# IRIS1304_v4_0.net
KiCad netlist of a schematic drawn in EAGLE
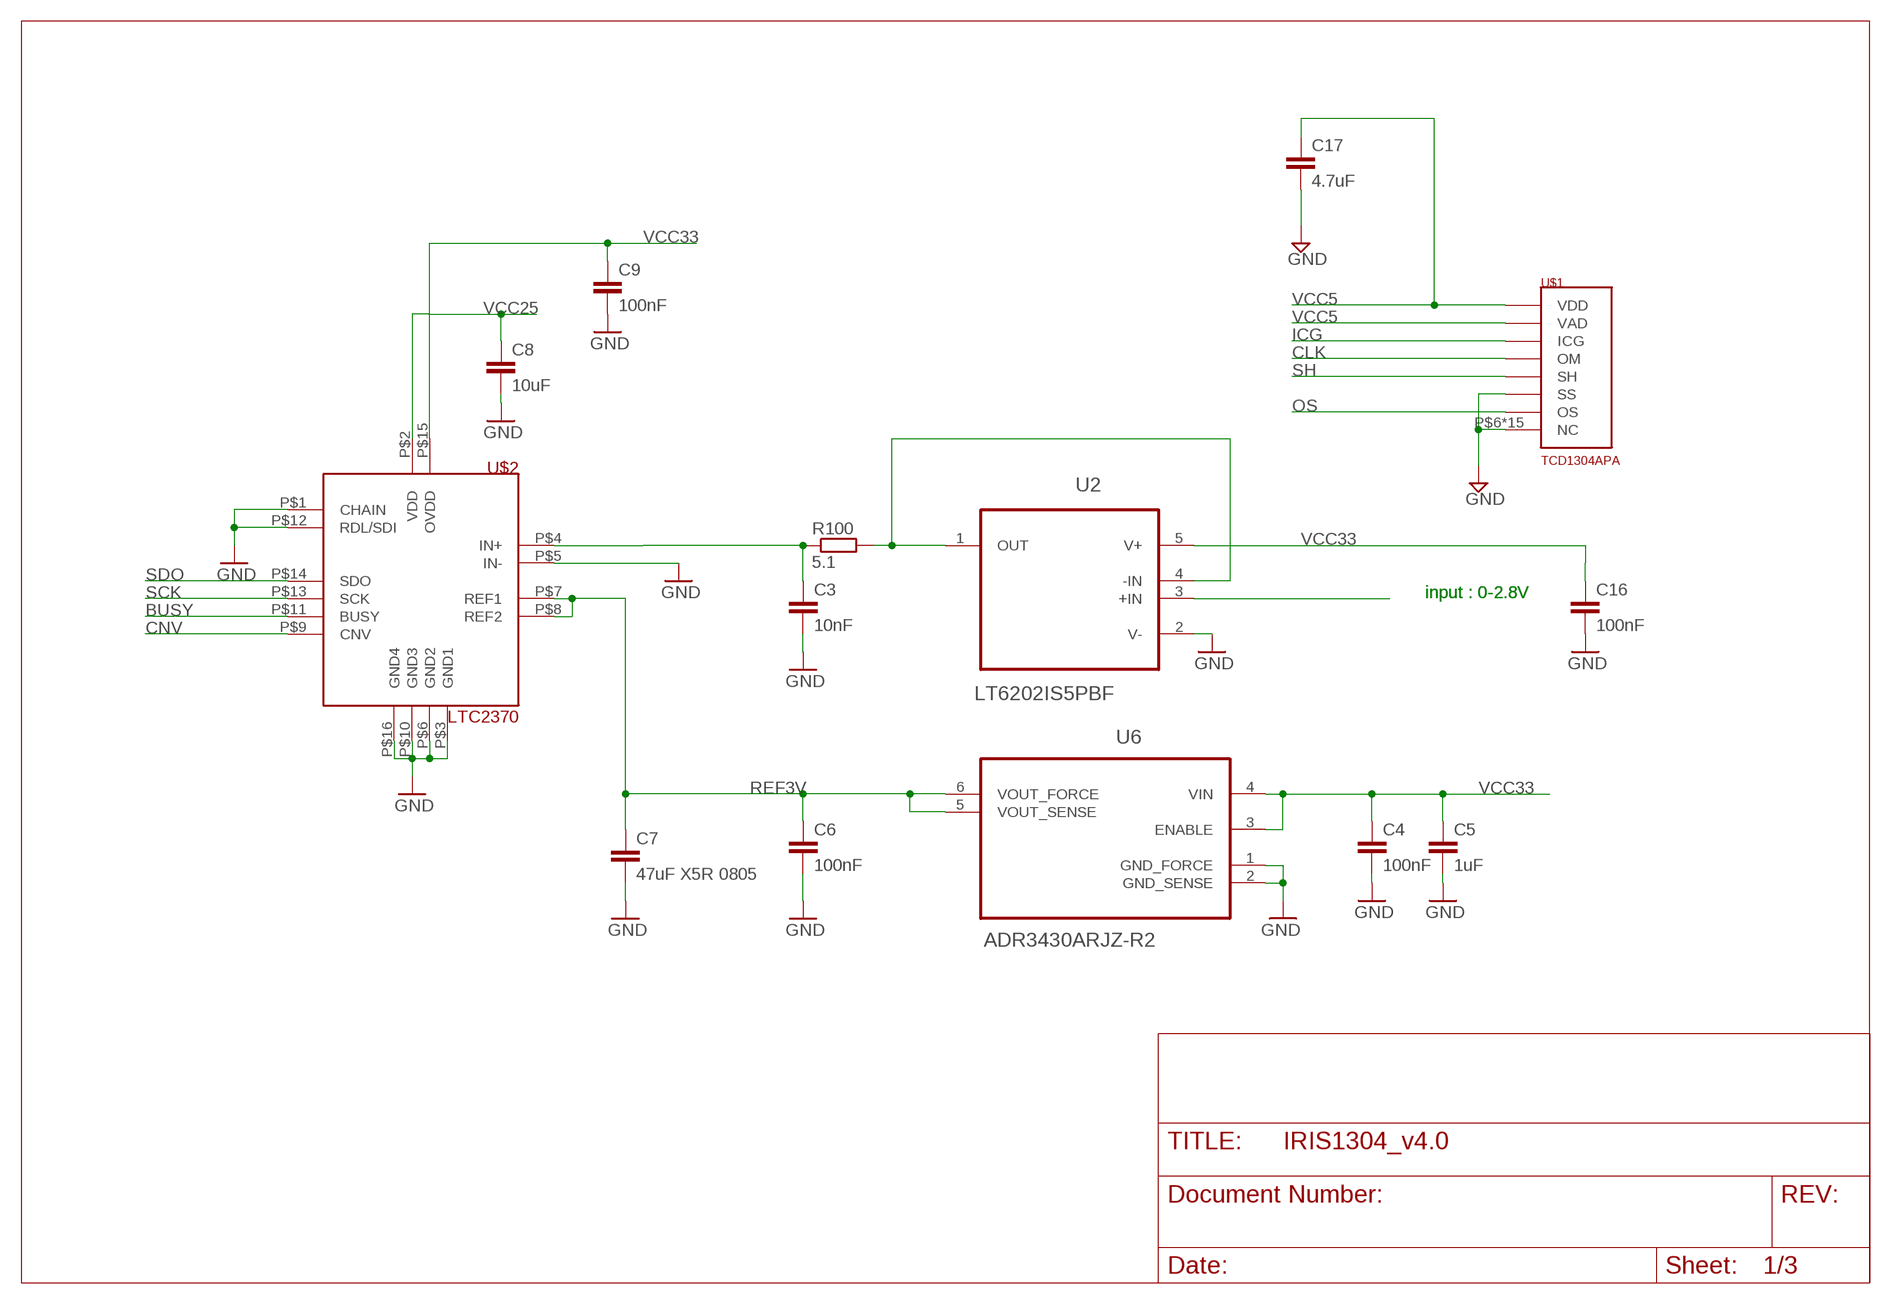
[diagram p0: schematic, sheet 1]
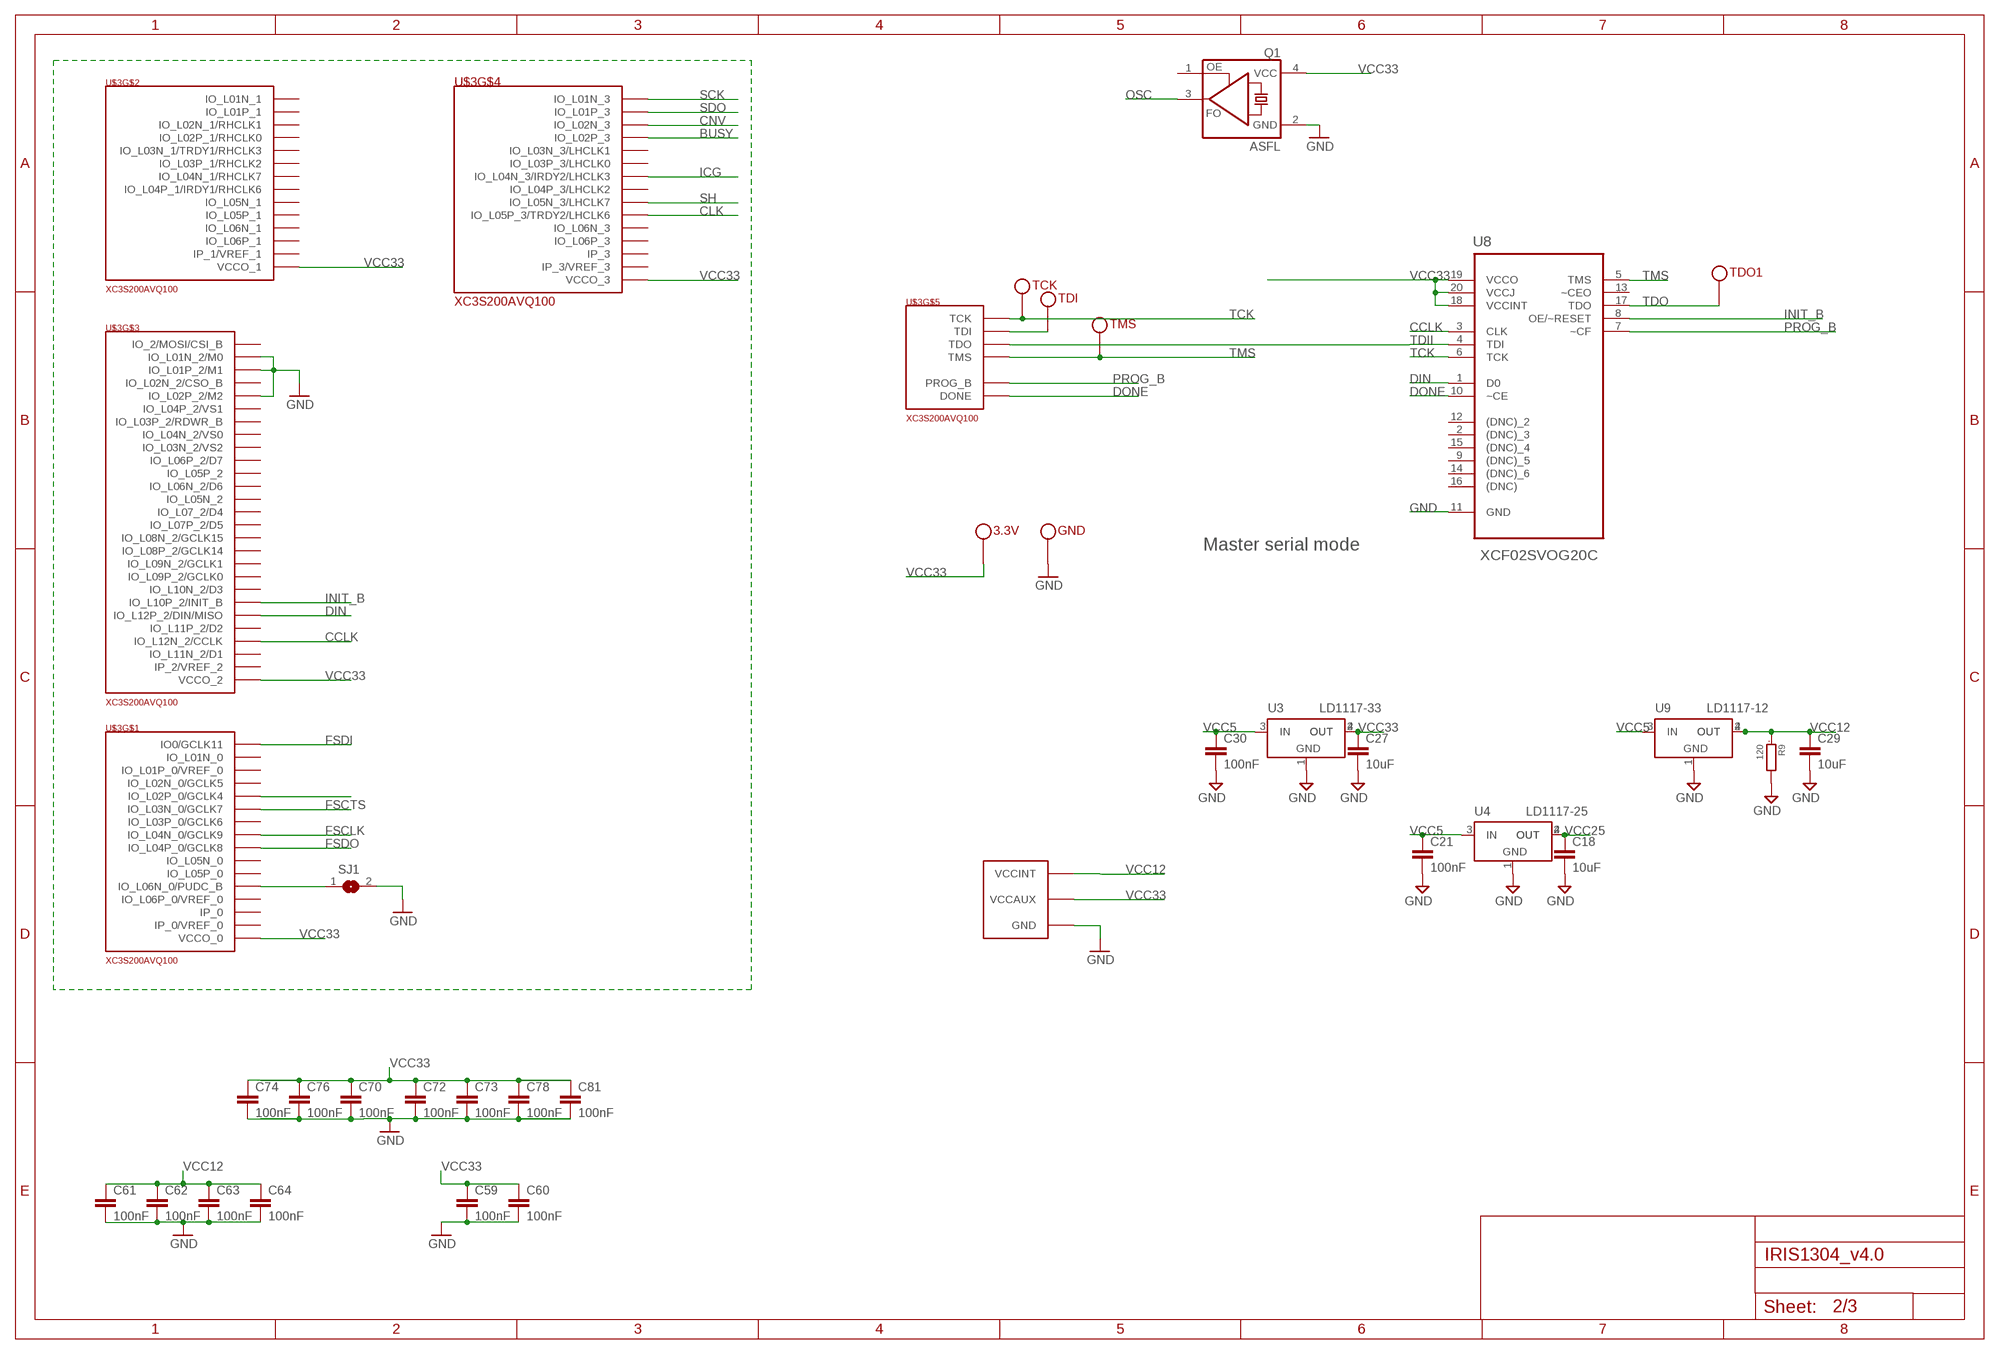
[diagram p1: schematic, sheet 2]
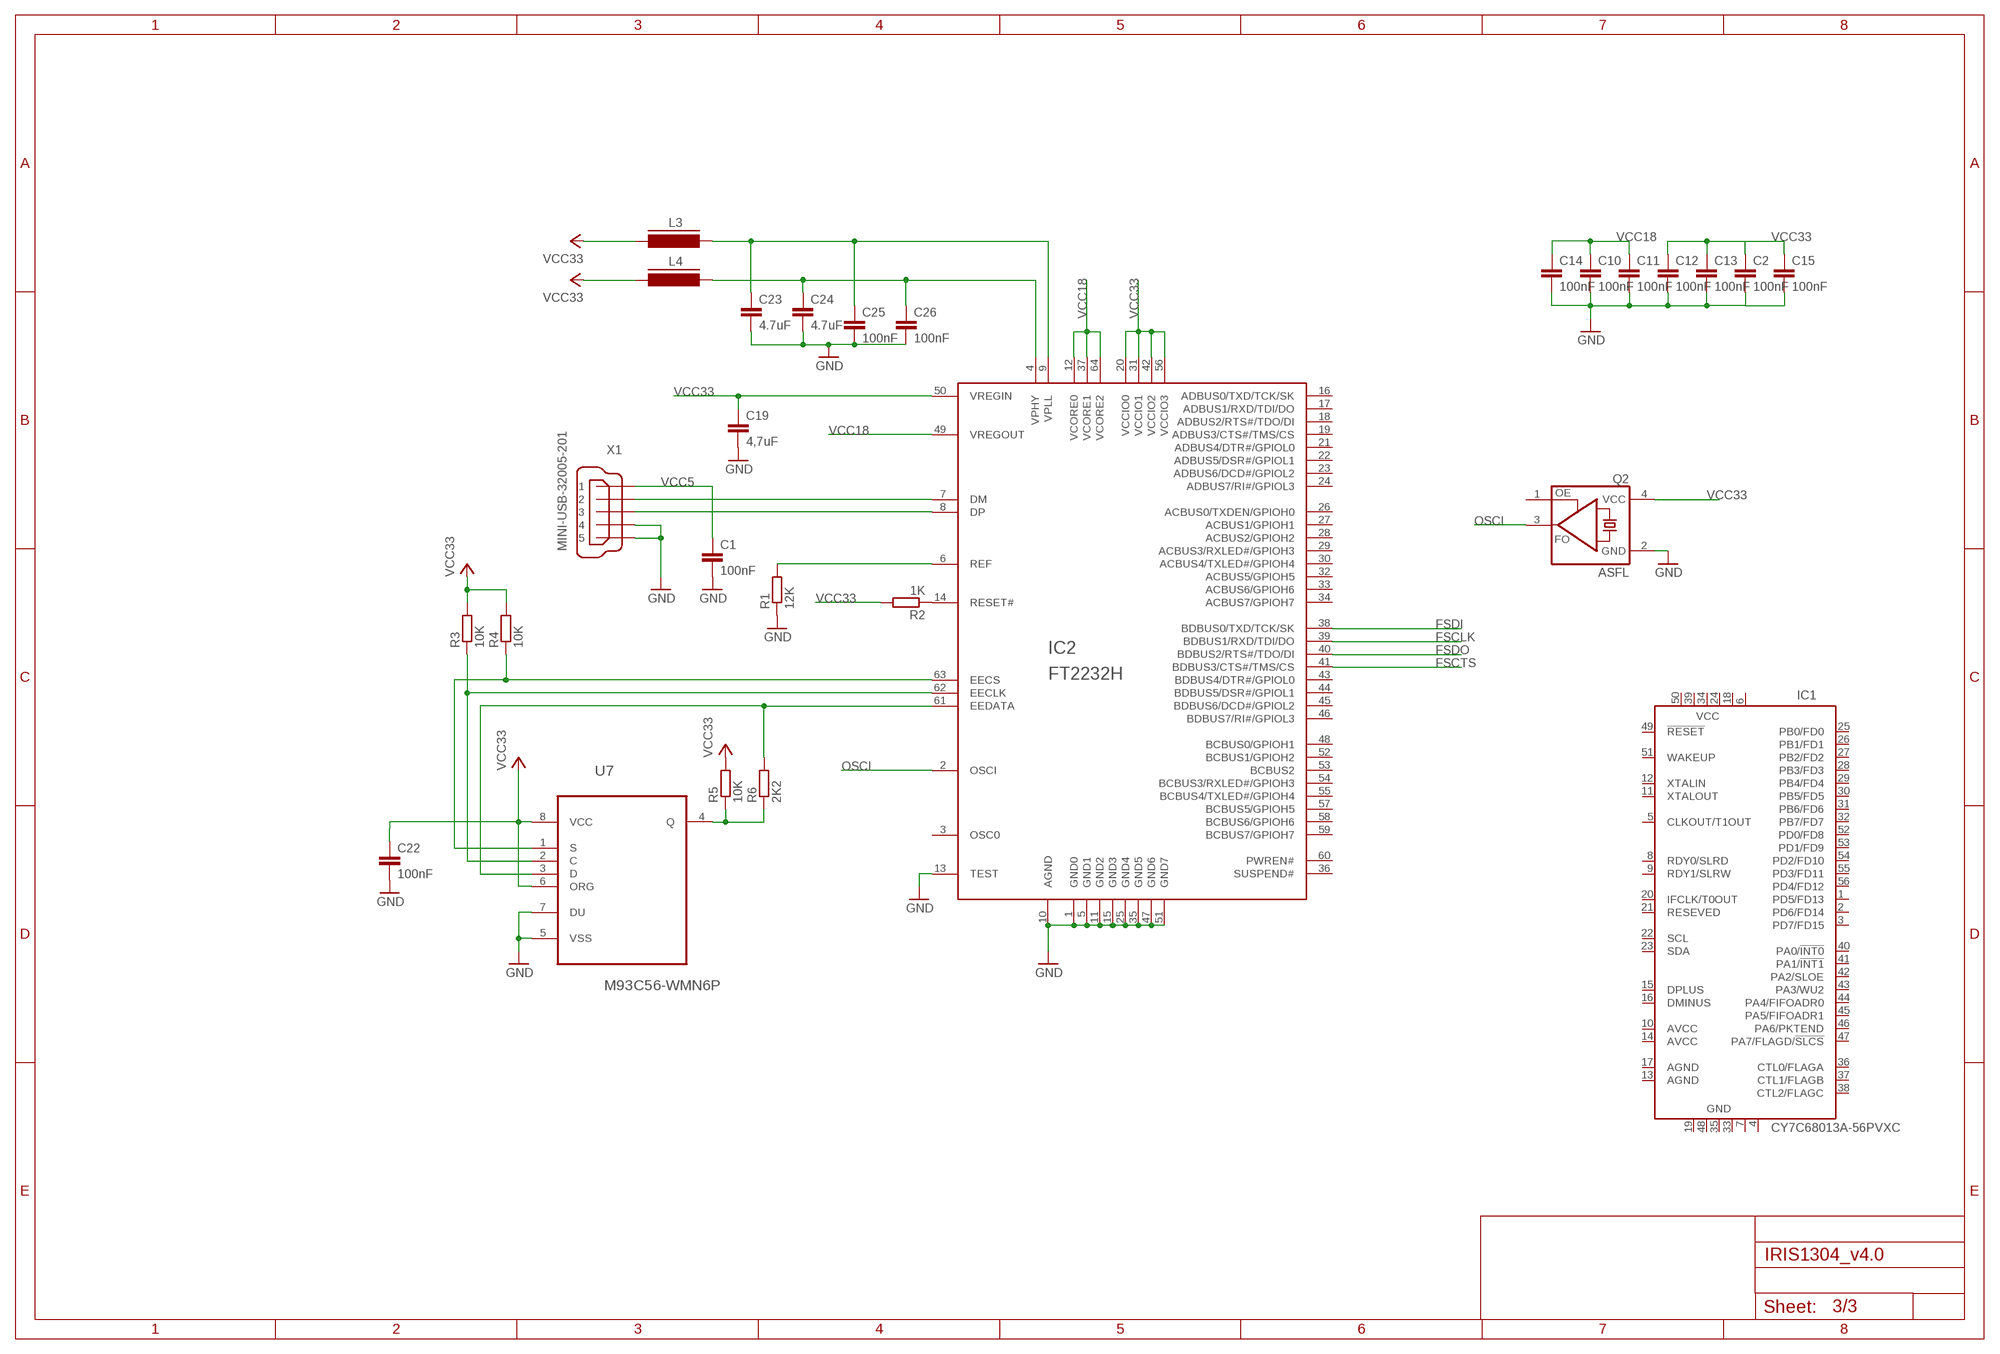
[diagram p2: schematic, sheet 3]

(export (version "E")
  (design (tool "Eeschema 10.0.6"))
  (components
    (comp (ref "C1")
      (value "100nF")
      (footprint "eagle-import:C0603")
      (fields (field (name "MF") "AVX") (field (name "MPN") "06033G104ZAT2A"))
      (libsource (lib "eagle-import") (part "C-EUC0603"))
    )
    (comp (ref "C2")
      (value "100nF")
      (footprint "eagle-import:C0603")
      (fields (field (name "MF") "AVX") (field (name "MPN") "06033G104ZAT2A"))
      (libsource (lib "eagle-import") (part "C-EUC0603"))
    )
    (comp (ref "C10")
      (value "100nF")
      (footprint "eagle-import:C0603")
      (fields (field (name "MF") "AVX") (field (name "MPN") "06033G104ZAT2A"))
      (libsource (lib "eagle-import") (part "C-EUC0603"))
    )
    (comp (ref "C11")
      (value "100nF")
      (footprint "eagle-import:C0603")
      (fields (field (name "MF") "AVX") (field (name "MPN") "06033G104ZAT2A"))
      (libsource (lib "eagle-import") (part "C-EUC0603"))
    )
    (comp (ref "C12")
      (value "100nF")
      (footprint "eagle-import:C0603")
      (fields (field (name "MF") "AVX") (field (name "MPN") "06033G104ZAT2A"))
      (libsource (lib "eagle-import") (part "C-EUC0603"))
    )
    (comp (ref "C13")
      (value "100nF")
      (footprint "eagle-import:C0603")
      (fields (field (name "MF") "AVX") (field (name "MPN") "06033G104ZAT2A"))
      (libsource (lib "eagle-import") (part "C-EUC0603"))
    )
    (comp (ref "C14")
      (value "100nF")
      (footprint "eagle-import:C0603")
      (fields (field (name "MF") "AVX") (field (name "MPN") "06033G104ZAT2A"))
      (libsource (lib "eagle-import") (part "C-EUC0603"))
    )
    (comp (ref "C15")
      (value "100nF")
      (footprint "eagle-import:C0603")
      (fields (field (name "MF") "AVX") (field (name "MPN") "06033G104ZAT2A"))
      (libsource (lib "eagle-import") (part "C-EUC0603"))
    )
    (comp (ref "C19")
      (value "4,7uF")
      (footprint "eagle-import:C0805")
      (fields (field (name "MF") "AVX") (field (name "MPN") "0805ZD335KAT2A"))
      (libsource (lib "eagle-import") (part "C-EUC0805"))
    )
    (comp (ref "C22")
      (value "100nF")
      (footprint "eagle-import:C0603")
      (fields (field (name "MF") "AVX") (field (name "MPN") "06033G104ZAT2A"))
      (libsource (lib "eagle-import") (part "C-EUC0603"))
    )
    (comp (ref "C23")
      (value "4.7uF")
      (footprint "eagle-import:C0603")
      (fields (field (name "MF") "YAGEO (PHYCOMP)") (field (name "MPN") "CC0603KRX5R6BB475"))
      (libsource (lib "eagle-import") (part "C-EUC0603"))
    )
    (comp (ref "C24")
      (value "4.7uF")
      (footprint "eagle-import:C0603")
      (fields (field (name "MF") "YAGEO (PHYCOMP)") (field (name "MPN") "CC0603KRX5R6BB475"))
      (libsource (lib "eagle-import") (part "C-EUC0603"))
    )
    (comp (ref "C25")
      (value "100nF")
      (footprint "eagle-import:C0603")
      (fields (field (name "MF") "AVX") (field (name "MPN") "06033G104ZAT2A"))
      (libsource (lib "eagle-import") (part "C-EUC0603"))
    )
    (comp (ref "C26")
      (value "100nF")
      (footprint "eagle-import:C0603")
      (fields (field (name "MF") "AVX") (field (name "MPN") "06033G104ZAT2A"))
      (libsource (lib "eagle-import") (part "C-EUC0603"))
    )
    (comp (ref "IC1")
      (value "CY7C68013A-56PVXC")
      (footprint "eagle-import:SSOP56")
      (fields (field (name "MF") "CYPRESS SEMICONDUCTOR CORPORAT"))
      (libsource (lib "eagle-import") (part "CY7C6801A-56PVXC3"))
    )
    (comp (ref "IC2")
      (value "FT2232H")
      (footprint "eagle-import:LQFP64")
      (fields (field (name "MF") "FTDI") (field (name "MPN") "FT2232HL-R"))
      (libsource (lib "eagle-import") (part "FT2232H"))
    )
    (comp (ref "L3")
      (value "FERRITE_BEAD805")
      (footprint "eagle-import:FB805")
      (libsource (lib "eagle-import") (part "FERRITE_BEAD805"))
    )
    (comp (ref "L4")
      (value "FERRITE_BEAD805")
      (footprint "eagle-import:FB805")
      (libsource (lib "eagle-import") (part "FERRITE_BEAD805"))
    )
    (comp (ref "Q2")
      (value "ASFL")
      (footprint "eagle-import:ASF")
      (fields
        (field (name "MPN") "ASFLM1-50.000MHZ-C-T")
        (field (name "MF") "ABRACON")
        (field (name "MPN_1") "ASFL1-12.000MHZ-EK-T")
        (field (name "OC_FARNELL") "7943088")
      )
      (libsource (lib "eagle-import") (part "ASFL"))
    )
    (comp (ref "R1")
      (value "12K")
      (footprint "eagle-import:R0603")
      (fields (field (name "MF") "TE CONNECTIVITY") (field (name "MPN") "CPF0201D12K1C1"))
      (libsource (lib "eagle-import") (part "R-EU_R0603"))
    )
    (comp (ref "R2")
      (value "1K")
      (footprint "eagle-import:R0603")
      (fields (field (name "MF") "VISHAY DRALORIC") (field (name "MPN") "CRCW06031K00FKEA"))
      (libsource (lib "eagle-import") (part "R-EU_R0603"))
    )
    (comp (ref "R3")
      (value "10K")
      (footprint "eagle-import:R0603")
      (fields (field (name "MF") "TE CONNECTIVITY / NEOHM") (field (name "MPN") "CPF0603F10KC1"))
      (libsource (lib "eagle-import") (part "R-EU_R0603"))
    )
    (comp (ref "R4")
      (value "10K")
      (footprint "eagle-import:R0603")
      (fields (field (name "MF") "TE CONNECTIVITY / NEOHM") (field (name "MPN") "CPF0603F10KC1"))
      (libsource (lib "eagle-import") (part "R-EU_R0603"))
    )
    (comp (ref "R5")
      (value "10K")
      (footprint "eagle-import:R0603")
      (fields (field (name "MF") "TE CONNECTIVITY / NEOHM") (field (name "MPN") "CPF0603F10KC1"))
      (libsource (lib "eagle-import") (part "R-EU_R0603"))
    )
    (comp (ref "R6")
      (value "2K2")
      (footprint "eagle-import:R0603")
      (fields (field (name "MF") "PANASONIC ELECTRONIC COMPONENTS") (field (name "MPN") "ERJP03F2201V"))
      (libsource (lib "eagle-import") (part "R-EU_R0603"))
    )
    (comp (ref "U7")
      (value "M93C56-WMN6P")
      (footprint "eagle-import:SOIC127P600X175-8N")
      (fields (field (name "MF") "STMICROELECTRONICS"))
      (libsource (lib "eagle-import") (part "M93C56-WMN6P"))
    )
    (comp (ref "X1")
      (value "MINI-USB-32005-201")
      (footprint "eagle-import:32005-201")
      (fields
        (field (name "MF") "WURTH ELEKTRONIK")
        (field (name "MPN") "65100516121")
        (field (name "OC_FARNELL") "1642036")
      )
      (libsource (lib "eagle-import") (part "MINI-USB-32005-201"))
    )
    (comp (ref "C3")
      (value "10nF")
      (footprint "eagle-import:C0603")
      (fields (field (name "MF") "AVX") (field (name "MPN") "06035G103ZAT2A"))
      (libsource (lib "eagle-import") (part "C-EUC0603"))
    )
    (comp (ref "C4")
      (value "100nF")
      (footprint "eagle-import:C0603")
      (fields (field (name "MF") "AVX") (field (name "MPN") "06033G104ZAT2A"))
      (libsource (lib "eagle-import") (part "C-EUC0603"))
    )
    (comp (ref "C5")
      (value "1uF")
      (footprint "eagle-import:C0603")
      (fields (field (name "MF") "KEMET") (field (name "MPN") "C0603C105K3PACTU"))
      (libsource (lib "eagle-import") (part "C-EUC0603"))
    )
    (comp (ref "C6")
      (value "100nF")
      (footprint "eagle-import:C0603")
      (fields (field (name "MF") "AVX") (field (name "MPN") "06033G104ZAT2A"))
      (libsource (lib "eagle-import") (part "C-EUC0603"))
    )
    (comp (ref "C7")
      (value "47uF X5R 0805")
      (footprint "eagle-import:C0805")
      (fields (field (name "MF") "KEMET") (field (name "MPN") "C0805C476M9PACTU"))
      (libsource (lib "eagle-import") (part "C-EUC0805"))
    )
    (comp (ref "C8")
      (value "10uF")
      (footprint "eagle-import:C0603")
      (fields (field (name "MF") "KEMET") (field (name "MPN") "C0603C106M9PACTU"))
      (libsource (lib "eagle-import") (part "C-EUC0603"))
    )
    (comp (ref "C9")
      (value "100nF")
      (footprint "eagle-import:C0603")
      (fields (field (name "MF") "AVX") (field (name "MPN") "06033G104ZAT2A"))
      (libsource (lib "eagle-import") (part "C-EUC0603"))
    )
    (comp (ref "C16")
      (value "100nF")
      (footprint "eagle-import:C0603")
      (fields (field (name "MF") "AVX") (field (name "MPN") "06033G104ZAT2A"))
      (libsource (lib "eagle-import") (part "C-EUC0603"))
    )
    (comp (ref "C17")
      (value "4.7uF")
      (footprint "eagle-import:C0603")
      (fields (field (name "MF") "YAGEO (PHYCOMP)") (field (name "MPN") "CC0603KRX5R6BB475"))
      (libsource (lib "eagle-import") (part "C-EUC0603"))
    )
    (comp (ref "R100")
      (value "5.1")
      (footprint "eagle-import:R0603")
      (fields (field (name "MF") "VISHAY DALE") (field (name "MPN") "CRCW06035R10FNEA"))
      (libsource (lib "eagle-import") (part "R-EU_R0603"))
    )
    (comp (ref "U$1")
      (value "TCD1304APA")
      (footprint "eagle-import:ILX511")
      (libsource (lib "eagle-import") (part "TCD1304APA"))
    )
    (comp (ref "U$2")
      (value "LTC2370")
      (footprint "eagle-import:MSOP-16")
      (fields (field (name "MF") "LINEAR TECHNOLOGY") (field (name "MPN") "LTC2370CMS-16"))
      (libsource (lib "eagle-import") (part "LTC2370"))
    )
    (comp (ref "U2")
      (value "LT6202IS5PBF")
      (footprint "eagle-import:SOT95P280X100-5N")
      (fields (field (name "MPN") "LT6202IS5#PBF") (field (name "MF") "LINEAR TECHNOLOGY"))
      (libsource (lib "eagle-import") (part "LT6202IS5PBF"))
    )
    (comp (ref "U6")
      (value "ADR3430ARJZ-R2")
      (footprint "eagle-import:SOT95P280X145-6N")
      (fields (field (name "MF") "ANALOG DEVICES"))
      (libsource (lib "eagle-import") (part "ADR3430ARJZ-R2"))
    )
    (comp (ref "3.3V")
      (value "TEST")
      (footprint "eagle-import:TEST")
      (fields (field (name "MF") "ITT CANNON") (field (name "MPN") "001-1007-040FB9"))
      (libsource (lib "eagle-import") (part "TEST"))
    )
    (comp (ref "C18")
      (value "10uF")
      (footprint "eagle-import:C0603")
      (fields (field (name "MF") "KEMET") (field (name "MPN") "C0603C106M9PACTU"))
      (libsource (lib "eagle-import") (part "C-EUC0603"))
    )
    (comp (ref "C21")
      (value "100nF")
      (footprint "eagle-import:C0603")
      (fields (field (name "MF") "AVX") (field (name "MPN") "06033G104ZAT2A"))
      (libsource (lib "eagle-import") (part "C-EUC0603"))
    )
    (comp (ref "C27")
      (value "10uF")
      (footprint "eagle-import:C0603")
      (fields (field (name "MF") "KEMET") (field (name "MPN") "C0603C106M9PACTU"))
      (libsource (lib "eagle-import") (part "C-EUC0603"))
    )
    (comp (ref "C29")
      (value "10uF")
      (footprint "eagle-import:C0603")
      (fields (field (name "MF") "KEMET") (field (name "MPN") "C0603C106M9PACTU"))
      (libsource (lib "eagle-import") (part "C-EUC0603"))
    )
    (comp (ref "C30")
      (value "100nF")
      (footprint "eagle-import:C0603")
      (fields (field (name "MF") "AVX") (field (name "MPN") "06033G104ZAT2A"))
      (libsource (lib "eagle-import") (part "C-EUC0603"))
    )
    (comp (ref "C59")
      (value "100nF")
      (footprint "eagle-import:C0603")
      (fields (field (name "MF") "AVX") (field (name "MPN") "06033G104ZAT2A"))
      (libsource (lib "eagle-import") (part "C-EUC0603"))
    )
    (comp (ref "C60")
      (value "100nF")
      (footprint "eagle-import:C0603")
      (fields (field (name "MF") "AVX") (field (name "MPN") "06033G104ZAT2A"))
      (libsource (lib "eagle-import") (part "C-EUC0603"))
    )
    (comp (ref "C61")
      (value "100nF")
      (footprint "eagle-import:C0603")
      (fields (field (name "MF") "AVX") (field (name "MPN") "06033G104ZAT2A"))
      (libsource (lib "eagle-import") (part "C-EUC0603"))
    )
    (comp (ref "C62")
      (value "100nF")
      (footprint "eagle-import:C0603")
      (fields (field (name "MF") "AVX") (field (name "MPN") "06033G104ZAT2A"))
      (libsource (lib "eagle-import") (part "C-EUC0603"))
    )
    (comp (ref "C63")
      (value "100nF")
      (footprint "eagle-import:C0603")
      (fields (field (name "MF") "AVX") (field (name "MPN") "06033G104ZAT2A"))
      (libsource (lib "eagle-import") (part "C-EUC0603"))
    )
    (comp (ref "C64")
      (value "100nF")
      (footprint "eagle-import:C0603")
      (fields (field (name "MF") "AVX") (field (name "MPN") "06033G104ZAT2A"))
      (libsource (lib "eagle-import") (part "C-EUC0603"))
    )
    (comp (ref "C70")
      (value "100nF")
      (footprint "eagle-import:C0603")
      (fields (field (name "MF") "AVX") (field (name "MPN") "06033G104ZAT2A"))
      (libsource (lib "eagle-import") (part "C-EUC0603"))
    )
    (comp (ref "C72")
      (value "100nF")
      (footprint "eagle-import:C0603")
      (fields (field (name "MF") "AVX") (field (name "MPN") "06033G104ZAT2A"))
      (libsource (lib "eagle-import") (part "C-EUC0603"))
    )
    (comp (ref "C73")
      (value "100nF")
      (footprint "eagle-import:C0603")
      (fields (field (name "MF") "AVX") (field (name "MPN") "06033G104ZAT2A"))
      (libsource (lib "eagle-import") (part "C-EUC0603"))
    )
    (comp (ref "C74")
      (value "100nF")
      (footprint "eagle-import:C0603")
      (fields (field (name "MF") "AVX") (field (name "MPN") "06033G104ZAT2A"))
      (libsource (lib "eagle-import") (part "C-EUC0603"))
    )
    (comp (ref "C76")
      (value "100nF")
      (footprint "eagle-import:C0603")
      (fields (field (name "MF") "AVX") (field (name "MPN") "06033G104ZAT2A"))
      (libsource (lib "eagle-import") (part "C-EUC0603"))
    )
    (comp (ref "C78")
      (value "100nF")
      (footprint "eagle-import:C0603")
      (fields (field (name "MF") "AVX") (field (name "MPN") "06033G104ZAT2A"))
      (libsource (lib "eagle-import") (part "C-EUC0603"))
    )
    (comp (ref "C81")
      (value "100nF")
      (footprint "eagle-import:C0603")
      (fields (field (name "MF") "AVX") (field (name "MPN") "06033G104ZAT2A"))
      (libsource (lib "eagle-import") (part "C-EUC0603"))
    )
    (comp (ref "GND")
      (value "TEST")
      (footprint "eagle-import:TEST")
      (fields (field (name "MF") "ITT CANNON") (field (name "MPN") "001-1007-040FB9"))
      (libsource (lib "eagle-import") (part "TEST"))
    )
    (comp (ref "Q1")
      (value "ASFL")
      (footprint "eagle-import:ASF")
      (fields
        (field (name "MPN") "ASFLM1-50.000MHZ-C-T")
        (field (name "MF") "ABRACON")
        (field (name "MPN_1") "ASFL1-12.000MHZ-EK-T")
        (field (name "OC_FARNELL") "7943088")
      )
      (libsource (lib "eagle-import") (part "ASFL"))
    )
    (comp (ref "R9")
      (value "120")
      (footprint "eagle-import:0805@1")
      (fields (field (name "MF") "TE CONNECTIVITY / SIGMA INDUCTORS") (field (name "MPN") "BMB2A0120AN1"))
      (libsource (lib "eagle-import") (part "R0805"))
    )
    (comp (ref "SJ1") (value "SJ") (footprint "eagle-import:SJ") (libsource (lib "eagle-import") (part "SJ")))
    (comp (ref "TCK")
      (value "TEST")
      (footprint "eagle-import:TEST")
      (fields (field (name "MF") "ITT CANNON") (field (name "MPN") "001-1007-040FB9"))
      (libsource (lib "eagle-import") (part "TEST"))
    )
    (comp (ref "TDI")
      (value "TEST")
      (footprint "eagle-import:TEST")
      (fields (field (name "MF") "ITT CANNON") (field (name "MPN") "001-1007-040FB9"))
      (libsource (lib "eagle-import") (part "TEST"))
    )
    (comp (ref "TDO1")
      (value "TEST")
      (footprint "eagle-import:TEST")
      (fields (field (name "MF") "ITT CANNON") (field (name "MPN") "001-1007-040FB9"))
      (libsource (lib "eagle-import") (part "TEST"))
    )
    (comp (ref "TMS")
      (value "TEST")
      (footprint "eagle-import:TEST")
      (fields (field (name "MF") "ITT CANNON") (field (name "MPN") "001-1007-040FB9"))
      (libsource (lib "eagle-import") (part "TEST"))
    )
    (comp (ref "U$3")
      (value "XC3S200AVQ100")
      (footprint "eagle-import:VQ100")
      (fields
        (field (name "MF") "XILINX")
        (field (name "MPN") "XC3S200A-4VQG100C")
        (field (name "OC_FARNELL") "1876204")
      )
      (libsource (lib "eagle-import") (part "XC3S200AVQ100"))
    )
    (comp (ref "U3")
      (value "LD1117-33")
      (footprint "eagle-import:SOT223")
      (fields (field (name "MF") "LINEAR TECHNOLOGY") (field (name "MPN") "LT1117CST-3.3#PBF"))
      (libsource (lib "eagle-import") (part "LD1117"))
    )
    (comp (ref "U4")
      (value "LD1117-25")
      (footprint "eagle-import:SOT223")
      (fields (field (name "MF") "STMICROELECTRONICS") (field (name "MPN") "LD1117S25TR"))
      (libsource (lib "eagle-import") (part "LD1117"))
    )
    (comp (ref "U8")
      (value "XCF02SVOG20C")
      (footprint "eagle-import:SOP65P640X119-20N")
      (fields (field (name "MF") "XILINX"))
      (libsource (lib "eagle-import") (part "XCF02SVOG20C"))
    )
    (comp (ref "U9")
      (value "LD1117-12")
      (footprint "eagle-import:SOT223")
      (fields (field (name "MF") "LINEAR TECHNOLOGY") (field (name "MPN") "LT1117IST#PBF"))
      (libsource (lib "eagle-import") (part "LD1117"))
    )
  )
  (nets
    (net (code "1") (name "BUSY") (class "Default")
      (node (ref "U$2") (pin "P$11") (pinfunction "BUSY_P$11") (pintype "bidirectional"))
      (node (ref "U$3") (pin "P5") (pinfunction "IO_L02P_3_P5") (pintype "bidirectional"))
    )
    (net (code "2") (name "CCLK") (class "Default")
      (node (ref "U$3") (pin "P53") (pinfunction "IO_L12N_2/CCLK_P53") (pintype "bidirectional"))
      (node (ref "U8") (pin "3") (pinfunction "CLK_3") (pintype "input"))
    )
    (net (code "3") (name "CLK") (class "Default")
      (node (ref "U$1") (pin "P$4") (pinfunction "OM_P$4") (pintype "bidirectional"))
      (node (ref "U$3") (pin "P15") (pinfunction "IO_L05P_3/TRDY2/LHCLK6_P15") (pintype "bidirectional"))
    )
    (net (code "4") (name "CNV") (class "Default")
      (node (ref "U$2") (pin "P$9") (pinfunction "CNV_P$9") (pintype "bidirectional"))
      (node (ref "U$3") (pin "P6") (pinfunction "IO_L02N_3_P6") (pintype "bidirectional"))
    )
    (net (code "5") (name "DIN") (class "Default")
      (node (ref "U$3") (pin "P51") (pinfunction "IO_L12P_2/DIN/MISO_P51") (pintype "bidirectional"))
      (node (ref "U8") (pin "1") (pinfunction "D0_1") (pintype "input"))
    )
    (net (code "6") (name "DONE") (class "Default")
      (node (ref "U$3") (pin "P54") (pinfunction "DONE_P54") (pintype "bidirectional"))
      (node (ref "U8") (pin "10") (pinfunction "~{CE}_10") (pintype "input"))
    )
    (net (code "7") (name "FSCLK") (class "Default")
      (node (ref "IC2") (pin "39") (pinfunction "BDBUS1/RXD/TDI/DO_39") (pintype "bidirectional"))
      (node (ref "U$3") (pin "P89") (pinfunction "IO_L04N_0/GCLK9_P89") (pintype "bidirectional"))
    )
    (net (code "8") (name "FSCTS") (class "Default")
      (node (ref "IC2") (pin "41") (pinfunction "BDBUS3/CTS#/TMS/CS_41") (pintype "bidirectional"))
      (node (ref "U$3") (pin "P86") (pinfunction "IO_L03N_0/GCLK7_P86") (pintype "bidirectional"))
    )
    (net (code "9") (name "FSDI") (class "Default")
      (node (ref "IC2") (pin "38") (pinfunction "BDBUS0/TXD/TCK/SK_38") (pintype "bidirectional"))
      (node (ref "U$3") (pin "P90") (pinfunction "IO0/GCLK11_P90") (pintype "bidirectional"))
    )
    (net (code "10") (name "FSDO") (class "Default")
      (node (ref "IC2") (pin "40") (pinfunction "BDBUS2/RTS#/TDO/DI_40") (pintype "bidirectional"))
      (node (ref "U$3") (pin "P88") (pinfunction "IO_L04P_0/GCLK8_P88") (pintype "bidirectional"))
    )
    (net (code "11") (name "GND") (class "Default")
      (node (ref "C1") (pin "2") (pinfunction "2_2") (pintype "passive"))
      (node (ref "C10") (pin "2") (pinfunction "2_2") (pintype "passive"))
      (node (ref "C11") (pin "2") (pinfunction "2_2") (pintype "passive"))
      (node (ref "C12") (pin "2") (pinfunction "2_2") (pintype "passive"))
      (node (ref "C13") (pin "2") (pinfunction "2_2") (pintype "passive"))
      (node (ref "C14") (pin "2") (pinfunction "2_2") (pintype "passive"))
      (node (ref "C15") (pin "2") (pinfunction "2_2") (pintype "passive"))
      (node (ref "C16") (pin "2") (pinfunction "2_2") (pintype "passive"))
      (node (ref "C17") (pin "2") (pinfunction "2_2") (pintype "passive"))
      (node (ref "C18") (pin "2") (pinfunction "2_2") (pintype "passive"))
      (node (ref "C19") (pin "2") (pinfunction "2_2") (pintype "passive"))
      (node (ref "C2") (pin "2") (pinfunction "2_2") (pintype "passive"))
      (node (ref "C21") (pin "2") (pinfunction "2_2") (pintype "passive"))
      (node (ref "C22") (pin "2") (pinfunction "2_2") (pintype "passive"))
      (node (ref "C23") (pin "2") (pinfunction "2_2") (pintype "passive"))
      (node (ref "C24") (pin "2") (pinfunction "2_2") (pintype "passive"))
      (node (ref "C25") (pin "2") (pinfunction "2_2") (pintype "passive"))
      (node (ref "C26") (pin "2") (pinfunction "2_2") (pintype "passive"))
      (node (ref "C27") (pin "2") (pinfunction "2_2") (pintype "passive"))
      (node (ref "C29") (pin "2") (pinfunction "2_2") (pintype "passive"))
      (node (ref "C3") (pin "2") (pinfunction "2_2") (pintype "passive"))
      (node (ref "C30") (pin "2") (pinfunction "2_2") (pintype "passive"))
      (node (ref "C4") (pin "2") (pinfunction "2_2") (pintype "passive"))
      (node (ref "C5") (pin "2") (pinfunction "2_2") (pintype "passive"))
      (node (ref "C59") (pin "2") (pinfunction "2_2") (pintype "passive"))
      (node (ref "C6") (pin "2") (pinfunction "2_2") (pintype "passive"))
      (node (ref "C60") (pin "2") (pinfunction "2_2") (pintype "passive"))
      (node (ref "C61") (pin "2") (pinfunction "2_2") (pintype "passive"))
      (node (ref "C62") (pin "2") (pinfunction "2_2") (pintype "passive"))
      (node (ref "C63") (pin "2") (pinfunction "2_2") (pintype "passive"))
      (node (ref "C64") (pin "2") (pinfunction "2_2") (pintype "passive"))
      (node (ref "C7") (pin "2") (pinfunction "2_2") (pintype "passive"))
      (node (ref "C70") (pin "2") (pinfunction "2_2") (pintype "passive"))
      (node (ref "C72") (pin "2") (pinfunction "2_2") (pintype "passive"))
      (node (ref "C73") (pin "2") (pinfunction "2_2") (pintype "passive"))
      (node (ref "C74") (pin "2") (pinfunction "2_2") (pintype "passive"))
      (node (ref "C76") (pin "2") (pinfunction "2_2") (pintype "passive"))
      (node (ref "C78") (pin "2") (pinfunction "2_2") (pintype "passive"))
      (node (ref "C8") (pin "2") (pinfunction "2_2") (pintype "passive"))
      (node (ref "C81") (pin "2") (pinfunction "2_2") (pintype "passive"))
      (node (ref "C9") (pin "2") (pinfunction "2_2") (pintype "passive"))
      (node (ref "GND") (pin "P$1") (pinfunction "P$1_P$1") (pintype "bidirectional"))
      (node (ref "IC2") (pin "1") (pinfunction "GND0_1") (pintype "bidirectional"))
      (node (ref "IC2") (pin "10") (pinfunction "AGND_10") (pintype "bidirectional"))
      (node (ref "IC2") (pin "11") (pinfunction "GND2_11") (pintype "bidirectional"))
      (node (ref "IC2") (pin "13") (pinfunction "TEST_13") (pintype "bidirectional"))
      (node (ref "IC2") (pin "15") (pinfunction "GND3_15") (pintype "bidirectional"))
      (node (ref "IC2") (pin "25") (pinfunction "GND4_25") (pintype "bidirectional"))
      (node (ref "IC2") (pin "35") (pinfunction "GND5_35") (pintype "bidirectional"))
      (node (ref "IC2") (pin "47") (pinfunction "GND6_47") (pintype "bidirectional"))
      (node (ref "IC2") (pin "5") (pinfunction "GND1_5") (pintype "bidirectional"))
      (node (ref "IC2") (pin "51") (pinfunction "GND7_51") (pintype "bidirectional"))
      (node (ref "Q1") (pin "2") (pinfunction "GND_2") (pintype "power_in"))
      (node (ref "Q2") (pin "2") (pinfunction "GND_2") (pintype "power_in"))
      (node (ref "R1") (pin "1") (pinfunction "1_1") (pintype "passive"))
      (node (ref "R9") (pin "2") (pinfunction "2_2") (pintype "passive"))
      (node (ref "SJ1") (pin "2") (pinfunction "2_2") (pintype "passive"))
      (node (ref "U$1") (pin "P$10") (pinfunction "NC_P$10") (pintype "bidirectional"))
      (node (ref "U$1") (pin "P$11") (pinfunction "NC_P$11") (pintype "bidirectional"))
      (node (ref "U$1") (pin "P$12") (pinfunction "NC_P$12") (pintype "bidirectional"))
      (node (ref "U$1") (pin "P$13") (pinfunction "NC_P$13") (pintype "bidirectional"))
      (node (ref "U$1") (pin "P$14") (pinfunction "NC_P$14") (pintype "bidirectional"))
      (node (ref "U$1") (pin "P$15") (pinfunction "NC_P$15") (pintype "bidirectional"))
      (node (ref "U$1") (pin "P$16") (pinfunction "NC_P$16") (pintype "bidirectional"))
      (node (ref "U$1") (pin "P$17") (pinfunction "NC_P$17") (pintype "bidirectional"))
      (node (ref "U$1") (pin "P$18") (pinfunction "NC_P$18") (pintype "bidirectional"))
      (node (ref "U$1") (pin "P$19") (pinfunction "NC_P$19") (pintype "bidirectional"))
      (node (ref "U$1") (pin "P$20") (pinfunction "NC_P$20") (pintype "bidirectional"))
      (node (ref "U$1") (pin "P$22") (pinfunction "SS_P$22") (pintype "bidirectional"))
      (node (ref "U$1") (pin "P$6") (pinfunction "NC_P$6") (pintype "bidirectional"))
      (node (ref "U$1") (pin "P$7") (pinfunction "NC_P$7") (pintype "bidirectional"))
      (node (ref "U$1") (pin "P$8") (pinfunction "NC_P$8") (pintype "bidirectional"))
      (node (ref "U$1") (pin "P$9") (pinfunction "NC_P$9") (pintype "bidirectional"))
      (node (ref "U$2") (pin "P$1") (pinfunction "CHAIN_P$1") (pintype "bidirectional"))
      (node (ref "U$2") (pin "P$10") (pinfunction "GND3_P$10") (pintype "bidirectional"))
      (node (ref "U$2") (pin "P$12") (pinfunction "RDL/SDI_P$12") (pintype "bidirectional"))
      (node (ref "U$2") (pin "P$16") (pinfunction "GND4_P$16") (pintype "bidirectional"))
      (node (ref "U$2") (pin "P$3") (pinfunction "GND1_P$3") (pintype "bidirectional"))
      (node (ref "U$2") (pin "P$5") (pinfunction "IN-_P$5") (pintype "bidirectional"))
      (node (ref "U$2") (pin "P$6") (pinfunction "GND2_P$6") (pintype "bidirectional"))
      (node (ref "U$3") (pin "P14") (pinfunction "GND_P14") (pintype "bidirectional"))
      (node (ref "U$3") (pin "P18") (pinfunction "GND_P18") (pintype "bidirectional"))
      (node (ref "U$3") (pin "P23") (pinfunction "IO_L01P_2/M1_P23") (pintype "bidirectional"))
      (node (ref "U$3") (pin "P24") (pinfunction "IO_L02P_2/M2_P24") (pintype "bidirectional"))
      (node (ref "U$3") (pin "P25") (pinfunction "IO_L01N_2/M0_P25") (pintype "bidirectional"))
      (node (ref "U$3") (pin "P42") (pinfunction "GND_P42") (pintype "bidirectional"))
      (node (ref "U$3") (pin "P47") (pinfunction "GND_P47") (pintype "bidirectional"))
      (node (ref "U$3") (pin "P58") (pinfunction "GND_P58") (pintype "bidirectional"))
      (node (ref "U$3") (pin "P63") (pinfunction "GND_P63") (pintype "bidirectional"))
      (node (ref "U$3") (pin "P69") (pinfunction "GND_P69") (pintype "bidirectional"))
      (node (ref "U$3") (pin "P74") (pinfunction "GND_P74") (pintype "bidirectional"))
      (node (ref "U$3") (pin "P8") (pinfunction "GND_P8") (pintype "bidirectional"))
      (node (ref "U$3") (pin "P80") (pinfunction "GND_P80") (pintype "bidirectional"))
      (node (ref "U$3") (pin "P87") (pinfunction "GND_P87") (pintype "bidirectional"))
      (node (ref "U$3") (pin "P91") (pinfunction "GND_P91") (pintype "bidirectional"))
      (node (ref "U$3") (pin "P95") (pinfunction "GND_P95") (pintype "bidirectional"))
      (node (ref "U2") (pin "2") (pinfunction "V-_2") (pintype "power_in"))
      (node (ref "U3") (pin "1") (pinfunction "GND_1") (pintype "power_in"))
      (node (ref "U4") (pin "1") (pinfunction "GND_1") (pintype "power_in"))
      (node (ref "U6") (pin "1") (pinfunction "GND_FORCE_1") (pintype "passive"))
      (node (ref "U6") (pin "2") (pinfunction "GND_SENSE_2") (pintype "passive"))
      (node (ref "U7") (pin "5") (pinfunction "VSS_5") (pintype "power_in"))
      (node (ref "U7") (pin "7") (pinfunction "DU_7") (pintype "input"))
      (node (ref "U8") (pin "11") (pinfunction "GND_11") (pintype "passive"))
      (node (ref "U9") (pin "1") (pinfunction "GND_1") (pintype "power_in"))
      (node (ref "X1") (pin "4") (pinfunction "4_4") (pintype "passive"))
      (node (ref "X1") (pin "5") (pinfunction "5_5") (pintype "passive"))
    )
    (net (code "12") (name "ICG") (class "Default")
      (node (ref "U$1") (pin "P$3") (pinfunction "ICG_P$3") (pintype "bidirectional"))
      (node (ref "U$3") (pin "P13") (pinfunction "IO_L04N_3/IRDY2/LHCLK3_P13") (pintype "bidirectional"))
    )
    (net (code "13") (name "INIT_B") (class "Default")
      (node (ref "U$3") (pin "P48") (pinfunction "IO_L10P_2/INIT_B_P48") (pintype "bidirectional"))
      (node (ref "U8") (pin "8") (pinfunction "OE/~{RESET}_8") (pintype "bidirectional"))
    )
    (net (code "14") (name "Net-(IC2-DM)") (class "Default")
      (node (ref "IC2") (pin "7") (pinfunction "DM_7") (pintype "bidirectional"))
      (node (ref "X1") (pin "2") (pinfunction "2_2") (pintype "passive"))
    )
    (net (code "15") (name "Net-(IC2-DP)") (class "Default")
      (node (ref "IC2") (pin "8") (pinfunction "DP_8") (pintype "bidirectional"))
      (node (ref "X1") (pin "3") (pinfunction "3_3") (pintype "passive"))
    )
    (net (code "16") (name "Net-(IC2-EECLK)") (class "Default")
      (node (ref "IC2") (pin "62") (pinfunction "EECLK_62") (pintype "bidirectional"))
      (node (ref "R3") (pin "1") (pinfunction "1_1") (pintype "passive"))
      (node (ref "U7") (pin "2") (pinfunction "C_2") (pintype "input"))
    )
    (net (code "17") (name "Net-(IC2-EECS)") (class "Default")
      (node (ref "IC2") (pin "63") (pinfunction "EECS_63") (pintype "bidirectional"))
      (node (ref "R4") (pin "1") (pinfunction "1_1") (pintype "passive"))
      (node (ref "U7") (pin "1") (pinfunction "S_1") (pintype "input"))
    )
    (net (code "18") (name "Net-(IC2-EEDATA)") (class "Default")
      (node (ref "IC2") (pin "61") (pinfunction "EEDATA_61") (pintype "bidirectional"))
      (node (ref "R6") (pin "2") (pinfunction "2_2") (pintype "passive"))
      (node (ref "U7") (pin "3") (pinfunction "D_3") (pintype "input"))
    )
    (net (code "19") (name "Net-(IC2-REF)") (class "Default")
      (node (ref "IC2") (pin "6") (pinfunction "REF_6") (pintype "bidirectional"))
      (node (ref "R1") (pin "2") (pinfunction "2_2") (pintype "passive"))
    )
    (net (code "20") (name "Net-(IC2-RESET#)") (class "Default")
      (node (ref "IC2") (pin "14") (pinfunction "RESET#_14") (pintype "bidirectional"))
      (node (ref "R2") (pin "1") (pinfunction "1_1") (pintype "passive"))
    )
    (net (code "21") (name "Net-(IC2-VPHY)") (class "Default")
      (node (ref "C24") (pin "1") (pinfunction "1_1") (pintype "passive"))
      (node (ref "C26") (pin "1") (pinfunction "1_1") (pintype "passive"))
      (node (ref "IC2") (pin "4") (pinfunction "VPHY_4") (pintype "bidirectional"))
      (node (ref "L4") (pin "1") (pinfunction "1_1") (pintype "passive"))
    )
    (net (code "22") (name "Net-(IC2-VPLL)") (class "Default")
      (node (ref "C23") (pin "1") (pinfunction "1_1") (pintype "passive"))
      (node (ref "C25") (pin "1") (pinfunction "1_1") (pintype "passive"))
      (node (ref "IC2") (pin "9") (pinfunction "VPLL_9") (pintype "bidirectional"))
      (node (ref "L3") (pin "1") (pinfunction "1_1") (pintype "passive"))
    )
    (net (code "23") (name "Net-(U$2-IN+)") (class "Default")
      (node (ref "C3") (pin "1") (pinfunction "1_1") (pintype "passive"))
      (node (ref "R100") (pin "1") (pinfunction "1_1") (pintype "passive"))
      (node (ref "U$2") (pin "P$4") (pinfunction "IN+_P$4") (pintype "bidirectional"))
    )
    (net (code "24") (name "Net-(U$3A-IO_L06N_0{slash}PUDC_B)") (class "Default")
      (node (ref "SJ1") (pin "1") (pinfunction "1_1") (pintype "passive"))
      (node (ref "U$3") (pin "P99") (pinfunction "IO_L06N_0/PUDC_B_P99") (pintype "bidirectional"))
    )
    (net (code "25") (name "Net-(U$3E-TDI)") (class "Default")
      (node (ref "TDI") (pin "P$1") (pinfunction "P$1_P$1") (pintype "bidirectional"))
      (node (ref "U$3") (pin "P2") (pinfunction "TDI_P2") (pintype "bidirectional"))
    )
    (net (code "26") (name "Net-(U2--IN)") (class "Default")
      (node (ref "R100") (pin "2") (pinfunction "2_2") (pintype "passive"))
      (node (ref "U2") (pin "1") (pinfunction "OUT_1") (pintype "output"))
      (node (ref "U2") (pin "4") (pinfunction "-IN_4") (pintype "input"))
    )
    (net (code "27") (name "Net-(U7-Q)") (class "Default")
      (node (ref "R5") (pin "1") (pinfunction "1_1") (pintype "passive"))
      (node (ref "R6") (pin "1") (pinfunction "1_1") (pintype "passive"))
      (node (ref "U7") (pin "4") (pinfunction "Q_4") (pintype "output"))
    )
    (net (code "28") (name "OS") (class "Default")
      (node (ref "U$1") (pin "P$21") (pinfunction "OS_P$21") (pintype "bidirectional"))
      (node (ref "U2") (pin "3") (pinfunction "+IN_3") (pintype "input"))
    )
    (net (code "29") (name "OSC") (class "Default")
      (node (ref "Q1") (pin "3") (pinfunction "FO_3") (pintype "output"))
      (node (ref "U$3") (pin "P83") (pinfunction "IO_L02P_0/GCLK4_P83") (pintype "bidirectional"))
    )
    (net (code "30") (name "OSCI") (class "Default")
      (node (ref "IC2") (pin "2") (pinfunction "OSCI_2") (pintype "bidirectional"))
      (node (ref "Q2") (pin "3") (pinfunction "FO_3") (pintype "output"))
    )
    (net (code "31") (name "PROG_B") (class "Default")
      (node (ref "U$3") (pin "P100") (pinfunction "PROG_B_P100") (pintype "bidirectional"))
      (node (ref "U8") (pin "7") (pinfunction "~{CF}_7") (pintype "bidirectional"))
    )
    (net (code "32") (name "REF3V") (class "Default")
      (node (ref "C6") (pin "1") (pinfunction "1_1") (pintype "passive"))
      (node (ref "C7") (pin "1") (pinfunction "1_1") (pintype "passive"))
      (node (ref "U$2") (pin "P$7") (pinfunction "REF1_P$7") (pintype "bidirectional"))
      (node (ref "U$2") (pin "P$8") (pinfunction "REF2_P$8") (pintype "bidirectional"))
      (node (ref "U6") (pin "5") (pinfunction "VOUT_SENSE_5") (pintype "output"))
      (node (ref "U6") (pin "6") (pinfunction "VOUT_FORCE_6") (pintype "output"))
    )
    (net (code "33") (name "SCK") (class "Default")
      (node (ref "U$2") (pin "P$13") (pinfunction "SCK_P$13") (pintype "bidirectional"))
      (node (ref "U$3") (pin "P4") (pinfunction "IO_L01N_3_P4") (pintype "bidirectional"))
    )
    (net (code "34") (name "SDO") (class "Default")
      (node (ref "U$2") (pin "P$14") (pinfunction "SDO_P$14") (pintype "bidirectional"))
      (node (ref "U$3") (pin "P3") (pinfunction "IO_L01P_3_P3") (pintype "bidirectional"))
    )
    (net (code "35") (name "SH") (class "Default")
      (node (ref "U$1") (pin "P$5") (pinfunction "SH_P$5") (pintype "bidirectional"))
      (node (ref "U$3") (pin "P16") (pinfunction "IO_L05N_3/LHCLK7_P16") (pintype "bidirectional"))
    )
    (net (code "36") (name "TCK") (class "Default")
      (node (ref "TCK") (pin "P$1") (pinfunction "P$1_P$1") (pintype "bidirectional"))
      (node (ref "U$3") (pin "P76") (pinfunction "TCK_P76") (pintype "bidirectional"))
      (node (ref "U8") (pin "6") (pinfunction "TCK_6") (pintype "input"))
    )
    (net (code "37") (name "TDII") (class "Default")
      (node (ref "U$3") (pin "P75") (pinfunction "TDO_P75") (pintype "bidirectional"))
      (node (ref "U8") (pin "4") (pinfunction "TDI_4") (pintype "input"))
    )
    (net (code "38") (name "TDO") (class "Default")
      (node (ref "TDO1") (pin "P$1") (pinfunction "P$1_P$1") (pintype "bidirectional"))
      (node (ref "U8") (pin "17") (pinfunction "TDO_17") (pintype "output"))
    )
    (net (code "39") (name "TMS") (class "Default")
      (node (ref "TMS") (pin "P$1") (pinfunction "P$1_P$1") (pintype "bidirectional"))
      (node (ref "U$3") (pin "P1") (pinfunction "TMS_P1") (pintype "bidirectional"))
      (node (ref "U8") (pin "5") (pinfunction "TMS_5") (pintype "input"))
    )
    (net (code "40") (name "VCC5") (class "Default")
      (node (ref "C1") (pin "1") (pinfunction "1_1") (pintype "passive"))
      (node (ref "C17") (pin "1") (pinfunction "1_1") (pintype "passive"))
      (node (ref "C21") (pin "1") (pinfunction "1_1") (pintype "passive"))
      (node (ref "C30") (pin "1") (pinfunction "1_1") (pintype "passive"))
      (node (ref "U$1") (pin "P$1") (pinfunction "VDD_P$1") (pintype "bidirectional"))
      (node (ref "U$1") (pin "P$2") (pinfunction "VAD_P$2") (pintype "bidirectional"))
      (node (ref "U3") (pin "3") (pinfunction "IN_3") (pintype "input"))
      (node (ref "U4") (pin "3") (pinfunction "IN_3") (pintype "input"))
      (node (ref "U9") (pin "3") (pinfunction "IN_3") (pintype "input"))
      (node (ref "X1") (pin "1") (pinfunction "1_1") (pintype "passive"))
    )
    (net (code "41") (name "VCC12") (class "Default")
      (node (ref "C29") (pin "1") (pinfunction "1_1") (pintype "passive"))
      (node (ref "C61") (pin "1") (pinfunction "1_1") (pintype "passive"))
      (node (ref "C62") (pin "1") (pinfunction "1_1") (pintype "passive"))
      (node (ref "C63") (pin "1") (pinfunction "1_1") (pintype "passive"))
      (node (ref "C64") (pin "1") (pinfunction "1_1") (pintype "passive"))
      (node (ref "R9") (pin "1") (pinfunction "1_1") (pintype "passive"))
      (node (ref "U$3") (pin "P17") (pinfunction "VCCINT_P17") (pintype "bidirectional"))
      (node (ref "U$3") (pin "P38") (pinfunction "VCCINT_P38") (pintype "bidirectional"))
      (node (ref "U$3") (pin "P66") (pinfunction "VCCINT_P66") (pintype "bidirectional"))
      (node (ref "U$3") (pin "P81") (pinfunction "VCCINT_P81") (pintype "bidirectional"))
      (node (ref "U9") (pin "2") (pinfunction "OUT_2") (pintype "output"))
      (node (ref "U9") (pin "4") (pinfunction "OUT_4") (pintype "output"))
    )
    (net (code "42") (name "VCC18") (class "Default")
      (node (ref "C10") (pin "1") (pinfunction "1_1") (pintype "passive"))
      (node (ref "C11") (pin "1") (pinfunction "1_1") (pintype "passive"))
      (node (ref "C14") (pin "1") (pinfunction "1_1") (pintype "passive"))
      (node (ref "IC2") (pin "12") (pinfunction "VCORE0_12") (pintype "bidirectional"))
      (node (ref "IC2") (pin "37") (pinfunction "VCORE1_37") (pintype "bidirectional"))
      (node (ref "IC2") (pin "49") (pinfunction "VREGOUT_49") (pintype "bidirectional"))
      (node (ref "IC2") (pin "64") (pinfunction "VCORE2_64") (pintype "bidirectional"))
    )
    (net (code "43") (name "VCC25") (class "Default")
      (node (ref "C18") (pin "1") (pinfunction "1_1") (pintype "passive"))
      (node (ref "C8") (pin "1") (pinfunction "1_1") (pintype "passive"))
      (node (ref "U$2") (pin "P$2") (pinfunction "VDD_P$2") (pintype "bidirectional"))
      (node (ref "U4") (pin "2") (pinfunction "OUT_2") (pintype "output"))
      (node (ref "U4") (pin "4") (pinfunction "OUT_4") (pintype "output"))
    )
    (net (code "44") (name "VCC33") (class "Default")
      (node (ref "3.3V") (pin "P$1") (pinfunction "P$1_P$1") (pintype "bidirectional"))
      (node (ref "C12") (pin "1") (pinfunction "1_1") (pintype "passive"))
      (node (ref "C13") (pin "1") (pinfunction "1_1") (pintype "passive"))
      (node (ref "C15") (pin "1") (pinfunction "1_1") (pintype "passive"))
      (node (ref "C16") (pin "1") (pinfunction "1_1") (pintype "passive"))
      (node (ref "C19") (pin "1") (pinfunction "1_1") (pintype "passive"))
      (node (ref "C2") (pin "1") (pinfunction "1_1") (pintype "passive"))
      (node (ref "C22") (pin "1") (pinfunction "1_1") (pintype "passive"))
      (node (ref "C27") (pin "1") (pinfunction "1_1") (pintype "passive"))
      (node (ref "C4") (pin "1") (pinfunction "1_1") (pintype "passive"))
      (node (ref "C5") (pin "1") (pinfunction "1_1") (pintype "passive"))
      (node (ref "C59") (pin "1") (pinfunction "1_1") (pintype "passive"))
      (node (ref "C60") (pin "1") (pinfunction "1_1") (pintype "passive"))
      (node (ref "C70") (pin "1") (pinfunction "1_1") (pintype "passive"))
      (node (ref "C72") (pin "1") (pinfunction "1_1") (pintype "passive"))
      (node (ref "C73") (pin "1") (pinfunction "1_1") (pintype "passive"))
      (node (ref "C74") (pin "1") (pinfunction "1_1") (pintype "passive"))
      (node (ref "C76") (pin "1") (pinfunction "1_1") (pintype "passive"))
      (node (ref "C78") (pin "1") (pinfunction "1_1") (pintype "passive"))
      (node (ref "C81") (pin "1") (pinfunction "1_1") (pintype "passive"))
      (node (ref "C9") (pin "1") (pinfunction "1_1") (pintype "passive"))
      (node (ref "IC2") (pin "20") (pinfunction "VCCIO0_20") (pintype "bidirectional"))
      (node (ref "IC2") (pin "31") (pinfunction "VCCIO1_31") (pintype "bidirectional"))
      (node (ref "IC2") (pin "42") (pinfunction "VCCIO2_42") (pintype "bidirectional"))
      (node (ref "IC2") (pin "50") (pinfunction "VREGIN_50") (pintype "bidirectional"))
      (node (ref "IC2") (pin "56") (pinfunction "VCCIO3_56") (pintype "bidirectional"))
      (node (ref "L3") (pin "2") (pinfunction "2_2") (pintype "passive"))
      (node (ref "L4") (pin "2") (pinfunction "2_2") (pintype "passive"))
      (node (ref "Q1") (pin "4") (pinfunction "VCC_4") (pintype "power_in"))
      (node (ref "Q2") (pin "4") (pinfunction "VCC_4") (pintype "power_in"))
      (node (ref "R2") (pin "2") (pinfunction "2_2") (pintype "passive"))
      (node (ref "R3") (pin "2") (pinfunction "2_2") (pintype "passive"))
      (node (ref "R4") (pin "2") (pinfunction "2_2") (pintype "passive"))
      (node (ref "R5") (pin "2") (pinfunction "2_2") (pintype "passive"))
      (node (ref "U$2") (pin "P$15") (pinfunction "OVDD_P$15") (pintype "bidirectional"))
      (node (ref "U$3") (pin "P11") (pinfunction "VCCO_3_P11") (pintype "bidirectional"))
      (node (ref "U$3") (pin "P22") (pinfunction "VCCAUX_P22") (pintype "bidirectional"))
      (node (ref "U$3") (pin "P26") (pinfunction "VCCO_2_P26") (pintype "bidirectional"))
      (node (ref "U$3") (pin "P45") (pinfunction "VCCO_2_P45") (pintype "bidirectional"))
      (node (ref "U$3") (pin "P55") (pinfunction "VCCAUX_P55") (pintype "bidirectional"))
      (node (ref "U$3") (pin "P67") (pinfunction "VCCO_1_P67") (pintype "bidirectional"))
      (node (ref "U$3") (pin "P79") (pinfunction "VCCO_0_P79") (pintype "bidirectional"))
      (node (ref "U$3") (pin "P92") (pinfunction "VCCAUX_P92") (pintype "bidirectional"))
      (node (ref "U$3") (pin "P96") (pinfunction "VCCO_0_P96") (pintype "bidirectional"))
      (node (ref "U2") (pin "5") (pinfunction "V+_5") (pintype "power_in"))
      (node (ref "U3") (pin "2") (pinfunction "OUT_2") (pintype "output"))
      (node (ref "U3") (pin "4") (pinfunction "OUT_4") (pintype "output"))
      (node (ref "U6") (pin "3") (pinfunction "ENABLE_3") (pintype "input"))
      (node (ref "U6") (pin "4") (pinfunction "VIN_4") (pintype "input"))
      (node (ref "U7") (pin "6") (pinfunction "ORG_6") (pintype "input"))
      (node (ref "U7") (pin "8") (pinfunction "VCC_8") (pintype "power_in"))
      (node (ref "U8") (pin "18") (pinfunction "VCCINT_18") (pintype "power_in"))
      (node (ref "U8") (pin "19") (pinfunction "VCCO_19") (pintype "power_in"))
      (node (ref "U8") (pin "20") (pinfunction "VCCJ_20") (pintype "power_in"))
    )
    (net (code "45") (name "unconnected-(IC1-AGND-Pad13)") (class "Default")
      (node (ref "IC1") (pin "13") (pinfunction "AGND_13") (pintype "input"))
    )
    (net (code "46") (name "unconnected-(IC1-AGND-Pad17)") (class "Default")
      (node (ref "IC1") (pin "17") (pinfunction "AGND_17") (pintype "input"))
    )
    (net (code "47") (name "unconnected-(IC1-AVCC-Pad10)") (class "Default")
      (node (ref "IC1") (pin "10") (pinfunction "AVCC_10") (pintype "input"))
    )
    (net (code "48") (name "unconnected-(IC1-AVCC-Pad14)") (class "Default")
      (node (ref "IC1") (pin "14") (pinfunction "AVCC_14") (pintype "input"))
    )
    (net (code "49") (name "unconnected-(IC1-CLKOUT{slash}T1OUT-Pad5)") (class "Default")
      (node (ref "IC1") (pin "5") (pinfunction "CLKOUT/T1OUT_5") (pintype "input"))
    )
    (net (code "50") (name "unconnected-(IC1-CTL0{slash}FLAGA-Pad36)") (class "Default")
      (node (ref "IC1") (pin "36") (pinfunction "CTL0/FLAGA_36") (pintype "output"))
    )
    (net (code "51") (name "unconnected-(IC1-CTL1{slash}FLAGB-Pad37)") (class "Default")
      (node (ref "IC1") (pin "37") (pinfunction "CTL1/FLAGB_37") (pintype "output"))
    )
    (net (code "52") (name "unconnected-(IC1-CTL2{slash}FLAGC-Pad38)") (class "Default")
      (node (ref "IC1") (pin "38") (pinfunction "CTL2/FLAGC_38") (pintype "output"))
    )
    (net (code "53") (name "unconnected-(IC1-DMINUS-Pad16)") (class "Default")
      (node (ref "IC1") (pin "16") (pinfunction "DMINUS_16") (pintype "bidirectional"))
    )
    (net (code "54") (name "unconnected-(IC1-DPLUS-Pad15)") (class "Default")
      (node (ref "IC1") (pin "15") (pinfunction "DPLUS_15") (pintype "bidirectional"))
    )
    (net (code "55") (name "unconnected-(IC1-GND-Pad4)") (class "Default")
      (node (ref "IC1") (pin "4") (pinfunction "GND_4") (pintype "input"))
    )
    (net (code "56") (name "unconnected-(IC1-GND-Pad7)") (class "Default")
      (node (ref "IC1") (pin "7") (pinfunction "GND_7") (pintype "input"))
    )
    (net (code "57") (name "unconnected-(IC1-GND-Pad19)") (class "Default")
      (node (ref "IC1") (pin "19") (pinfunction "GND_19") (pintype "input"))
    )
    (net (code "58") (name "unconnected-(IC1-GND-Pad33)") (class "Default")
      (node (ref "IC1") (pin "33") (pinfunction "GND_33") (pintype "input"))
    )
    (net (code "59") (name "unconnected-(IC1-GND-Pad35)") (class "Default")
      (node (ref "IC1") (pin "35") (pinfunction "GND_35") (pintype "input"))
    )
    (net (code "60") (name "unconnected-(IC1-GND-Pad48)") (class "Default")
      (node (ref "IC1") (pin "48") (pinfunction "GND_48") (pintype "input"))
    )
    (net (code "61") (name "unconnected-(IC1-IFCLK{slash}T0OUT-Pad20)") (class "Default")
      (node (ref "IC1") (pin "20") (pinfunction "IFCLK/T0OUT_20") (pintype "bidirectional"))
    )
    (net (code "62") (name "unconnected-(IC1-PA0{slash}~{INT0}-Pad40)") (class "Default")
      (node (ref "IC1") (pin "40") (pinfunction "PA0/~{INT0}_40") (pintype "bidirectional"))
    )
    (net (code "63") (name "unconnected-(IC1-PA1{slash}~{INT1}-Pad41)") (class "Default")
      (node (ref "IC1") (pin "41") (pinfunction "PA1/~{INT1}_41") (pintype "bidirectional"))
    )
    (net (code "64") (name "unconnected-(IC1-PA2{slash}SLOE-Pad42)") (class "Default")
      (node (ref "IC1") (pin "42") (pinfunction "PA2/SLOE_42") (pintype "bidirectional"))
    )
    (net (code "65") (name "unconnected-(IC1-PA3{slash}WU2-Pad43)") (class "Default")
      (node (ref "IC1") (pin "43") (pinfunction "PA3/WU2_43") (pintype "bidirectional"))
    )
    (net (code "66") (name "unconnected-(IC1-PA4{slash}FIFOADR0-Pad44)") (class "Default")
      (node (ref "IC1") (pin "44") (pinfunction "PA4/FIFOADR0_44") (pintype "bidirectional"))
    )
    (net (code "67") (name "unconnected-(IC1-PA5{slash}FIFOADR1-Pad45)") (class "Default")
      (node (ref "IC1") (pin "45") (pinfunction "PA5/FIFOADR1_45") (pintype "bidirectional"))
    )
    (net (code "68") (name "unconnected-(IC1-PA6{slash}PKTEND-Pad46)") (class "Default")
      (node (ref "IC1") (pin "46") (pinfunction "PA6/PKTEND_46") (pintype "bidirectional"))
    )
    (net (code "69") (name "unconnected-(IC1-PA7{slash}FLAGD{slash}~{SLCS}-Pad47)") (class "Default")
      (node (ref "IC1") (pin "47") (pinfunction "PA7/FLAGD/~{SLCS}_47") (pintype "bidirectional"))
    )
    (net (code "70") (name "unconnected-(IC1-PB0{slash}FD0-Pad25)") (class "Default")
      (node (ref "IC1") (pin "25") (pinfunction "PB0/FD0_25") (pintype "bidirectional"))
    )
    (net (code "71") (name "unconnected-(IC1-PB1{slash}FD1-Pad26)") (class "Default")
      (node (ref "IC1") (pin "26") (pinfunction "PB1/FD1_26") (pintype "bidirectional"))
    )
    (net (code "72") (name "unconnected-(IC1-PB2{slash}FD2-Pad27)") (class "Default")
      (node (ref "IC1") (pin "27") (pinfunction "PB2/FD2_27") (pintype "bidirectional"))
    )
    (net (code "73") (name "unconnected-(IC1-PB3{slash}FD3-Pad28)") (class "Default")
      (node (ref "IC1") (pin "28") (pinfunction "PB3/FD3_28") (pintype "bidirectional"))
    )
    (net (code "74") (name "unconnected-(IC1-PB4{slash}FD4-Pad29)") (class "Default")
      (node (ref "IC1") (pin "29") (pinfunction "PB4/FD4_29") (pintype "bidirectional"))
    )
    (net (code "75") (name "unconnected-(IC1-PB5{slash}FD5-Pad30)") (class "Default")
      (node (ref "IC1") (pin "30") (pinfunction "PB5/FD5_30") (pintype "bidirectional"))
    )
    (net (code "76") (name "unconnected-(IC1-PB6{slash}FD6-Pad31)") (class "Default")
      (node (ref "IC1") (pin "31") (pinfunction "PB6/FD6_31") (pintype "bidirectional"))
    )
    (net (code "77") (name "unconnected-(IC1-PB7{slash}FD7-Pad32)") (class "Default")
      (node (ref "IC1") (pin "32") (pinfunction "PB7/FD7_32") (pintype "bidirectional"))
    )
    (net (code "78") (name "unconnected-(IC1-PD0{slash}FD8-Pad52)") (class "Default")
      (node (ref "IC1") (pin "52") (pinfunction "PD0/FD8_52") (pintype "bidirectional"))
    )
    (net (code "79") (name "unconnected-(IC1-PD1{slash}FD9-Pad53)") (class "Default")
      (node (ref "IC1") (pin "53") (pinfunction "PD1/FD9_53") (pintype "bidirectional"))
    )
    (net (code "80") (name "unconnected-(IC1-PD2{slash}FD10-Pad54)") (class "Default")
      (node (ref "IC1") (pin "54") (pinfunction "PD2/FD10_54") (pintype "bidirectional"))
    )
    (net (code "81") (name "unconnected-(IC1-PD3{slash}FD11-Pad55)") (class "Default")
      (node (ref "IC1") (pin "55") (pinfunction "PD3/FD11_55") (pintype "bidirectional"))
    )
    (net (code "82") (name "unconnected-(IC1-PD4{slash}FD12-Pad56)") (class "Default")
      (node (ref "IC1") (pin "56") (pinfunction "PD4/FD12_56") (pintype "bidirectional"))
    )
    (net (code "83") (name "unconnected-(IC1-PD5{slash}FD13-Pad1)") (class "Default")
      (node (ref "IC1") (pin "1") (pinfunction "PD5/FD13_1") (pintype "bidirectional"))
    )
    (net (code "84") (name "unconnected-(IC1-PD6{slash}FD14-Pad2)") (class "Default")
      (node (ref "IC1") (pin "2") (pinfunction "PD6/FD14_2") (pintype "bidirectional"))
    )
    (net (code "85") (name "unconnected-(IC1-PD7{slash}FD15-Pad3)") (class "Default")
      (node (ref "IC1") (pin "3") (pinfunction "PD7/FD15_3") (pintype "bidirectional"))
    )
    (net (code "86") (name "unconnected-(IC1-RDY0{slash}SLRD-Pad8)") (class "Default")
      (node (ref "IC1") (pin "8") (pinfunction "RDY0/SLRD_8") (pintype "input"))
    )
    (net (code "87") (name "unconnected-(IC1-RDY1{slash}SLRW-Pad9)") (class "Default")
      (node (ref "IC1") (pin "9") (pinfunction "RDY1/SLRW_9") (pintype "input"))
    )
    (net (code "88") (name "unconnected-(IC1-RESEVED-Pad21)") (class "Default")
      (node (ref "IC1") (pin "21") (pinfunction "RESEVED_21") (pintype "input"))
    )
    (net (code "89") (name "unconnected-(IC1-SCL-Pad22)") (class "Default")
      (node (ref "IC1") (pin "22") (pinfunction "SCL_22") (pintype "output"))
    )
    (net (code "90") (name "unconnected-(IC1-SDA-Pad23)") (class "Default")
      (node (ref "IC1") (pin "23") (pinfunction "SDA_23") (pintype "bidirectional"))
    )
    (net (code "91") (name "unconnected-(IC1-VCC-Pad6)") (class "Default")
      (node (ref "IC1") (pin "6") (pinfunction "VCC_6") (pintype "input"))
    )
    (net (code "92") (name "unconnected-(IC1-VCC-Pad18)") (class "Default")
      (node (ref "IC1") (pin "18") (pinfunction "VCC_18") (pintype "input"))
    )
    (net (code "93") (name "unconnected-(IC1-VCC-Pad24)") (class "Default")
      (node (ref "IC1") (pin "24") (pinfunction "VCC_24") (pintype "input"))
    )
    (net (code "94") (name "unconnected-(IC1-VCC-Pad34)") (class "Default")
      (node (ref "IC1") (pin "34") (pinfunction "VCC_34") (pintype "input"))
    )
    (net (code "95") (name "unconnected-(IC1-VCC-Pad39)") (class "Default")
      (node (ref "IC1") (pin "39") (pinfunction "VCC_39") (pintype "input"))
    )
    (net (code "96") (name "unconnected-(IC1-VCC-Pad50)") (class "Default")
      (node (ref "IC1") (pin "50") (pinfunction "VCC_50") (pintype "input"))
    )
    (net (code "97") (name "unconnected-(IC1-WAKEUP-Pad51)") (class "Default")
      (node (ref "IC1") (pin "51") (pinfunction "WAKEUP_51") (pintype "input"))
    )
    (net (code "98") (name "unconnected-(IC1-XTALIN-Pad12)") (class "Default")
      (node (ref "IC1") (pin "12") (pinfunction "XTALIN_12") (pintype "input"))
    )
    (net (code "99") (name "unconnected-(IC1-XTALOUT-Pad11)") (class "Default")
      (node (ref "IC1") (pin "11") (pinfunction "XTALOUT_11") (pintype "input"))
    )
    (net (code "100") (name "unconnected-(IC1-~{RESET}-Pad49)") (class "Default")
      (node (ref "IC1") (pin "49") (pinfunction "~{RESET}_49") (pintype "input"))
    )
    (net (code "101") (name "unconnected-(IC2-ACBUS0{slash}TXDEN{slash}GPIOH0-Pad26)") (class "Default")
      (node (ref "IC2") (pin "26") (pinfunction "ACBUS0/TXDEN/GPIOH0_26") (pintype "bidirectional"))
    )
    (net (code "102") (name "unconnected-(IC2-ACBUS1{slash}GPIOH1-Pad27)") (class "Default")
      (node (ref "IC2") (pin "27") (pinfunction "ACBUS1/GPIOH1_27") (pintype "bidirectional"))
    )
    (net (code "103") (name "unconnected-(IC2-ACBUS2{slash}GPIOH2-Pad28)") (class "Default")
      (node (ref "IC2") (pin "28") (pinfunction "ACBUS2/GPIOH2_28") (pintype "bidirectional"))
    )
    (net (code "104") (name "unconnected-(IC2-ACBUS3{slash}RXLED#{slash}GPIOH3-Pad29)") (class "Default")
      (node (ref "IC2") (pin "29") (pinfunction "ACBUS3/RXLED#/GPIOH3_29") (pintype "bidirectional"))
    )
    (net (code "105") (name "unconnected-(IC2-ACBUS4{slash}TXLED#{slash}GPIOH4-Pad30)") (class "Default")
      (node (ref "IC2") (pin "30") (pinfunction "ACBUS4/TXLED#/GPIOH4_30") (pintype "bidirectional"))
    )
    (net (code "106") (name "unconnected-(IC2-ACBUS5{slash}GPIOH5-Pad32)") (class "Default")
      (node (ref "IC2") (pin "32") (pinfunction "ACBUS5/GPIOH5_32") (pintype "bidirectional"))
    )
    (net (code "107") (name "unconnected-(IC2-ACBUS6{slash}GPIOH6-Pad33)") (class "Default")
      (node (ref "IC2") (pin "33") (pinfunction "ACBUS6/GPIOH6_33") (pintype "bidirectional"))
    )
    (net (code "108") (name "unconnected-(IC2-ACBUS7{slash}GPIOH7-Pad34)") (class "Default")
      (node (ref "IC2") (pin "34") (pinfunction "ACBUS7/GPIOH7_34") (pintype "bidirectional"))
    )
    (net (code "109") (name "unconnected-(IC2-ADBUS0{slash}TXD{slash}TCK{slash}SK-Pad16)") (class "Default")
      (node (ref "IC2") (pin "16") (pinfunction "ADBUS0/TXD/TCK/SK_16") (pintype "bidirectional"))
    )
    (net (code "110") (name "unconnected-(IC2-ADBUS1{slash}RXD{slash}TDI{slash}DO-Pad17)") (class "Default")
      (node (ref "IC2") (pin "17") (pinfunction "ADBUS1/RXD/TDI/DO_17") (pintype "bidirectional"))
    )
    (net (code "111") (name "unconnected-(IC2-ADBUS2{slash}RTS#{slash}TDO{slash}DI-Pad18)") (class "Default")
      (node (ref "IC2") (pin "18") (pinfunction "ADBUS2/RTS#/TDO/DI_18") (pintype "bidirectional"))
    )
    (net (code "112") (name "unconnected-(IC2-ADBUS3{slash}CTS#{slash}TMS{slash}CS-Pad19)") (class "Default")
      (node (ref "IC2") (pin "19") (pinfunction "ADBUS3/CTS#/TMS/CS_19") (pintype "bidirectional"))
    )
    (net (code "113") (name "unconnected-(IC2-ADBUS4{slash}DTR#{slash}GPIOL0-Pad21)") (class "Default")
      (node (ref "IC2") (pin "21") (pinfunction "ADBUS4/DTR#/GPIOL0_21") (pintype "bidirectional"))
    )
    (net (code "114") (name "unconnected-(IC2-ADBUS5{slash}DSR#{slash}GPIOL1-Pad22)") (class "Default")
      (node (ref "IC2") (pin "22") (pinfunction "ADBUS5/DSR#/GPIOL1_22") (pintype "bidirectional"))
    )
    (net (code "115") (name "unconnected-(IC2-ADBUS6{slash}DCD#{slash}GPIOL2-Pad23)") (class "Default")
      (node (ref "IC2") (pin "23") (pinfunction "ADBUS6/DCD#/GPIOL2_23") (pintype "bidirectional"))
    )
    (net (code "116") (name "unconnected-(IC2-ADBUS7{slash}RI#{slash}GPIOL3-Pad24)") (class "Default")
      (node (ref "IC2") (pin "24") (pinfunction "ADBUS7/RI#/GPIOL3_24") (pintype "bidirectional"))
    )
    (net (code "117") (name "unconnected-(IC2-BCBUS0{slash}GPIOH1-Pad48)") (class "Default")
      (node (ref "IC2") (pin "48") (pinfunction "BCBUS0/GPIOH1_48") (pintype "bidirectional"))
    )
    (net (code "118") (name "unconnected-(IC2-BCBUS1{slash}GPIOH2-Pad52)") (class "Default")
      (node (ref "IC2") (pin "52") (pinfunction "BCBUS1/GPIOH2_52") (pintype "bidirectional"))
    )
    (net (code "119") (name "unconnected-(IC2-BCBUS2-Pad53)") (class "Default")
      (node (ref "IC2") (pin "53") (pinfunction "BCBUS2_53") (pintype "bidirectional"))
    )
    (net (code "120") (name "unconnected-(IC2-BCBUS3{slash}RXLED#{slash}GPIOH3-Pad54)") (class "Default")
      (node (ref "IC2") (pin "54") (pinfunction "BCBUS3/RXLED#/GPIOH3_54") (pintype "bidirectional"))
    )
    (net (code "121") (name "unconnected-(IC2-BCBUS4{slash}TXLED#{slash}GPIOH4-Pad55)") (class "Default")
      (node (ref "IC2") (pin "55") (pinfunction "BCBUS4/TXLED#/GPIOH4_55") (pintype "bidirectional"))
    )
    (net (code "122") (name "unconnected-(IC2-BCBUS5{slash}GPIOH5-Pad57)") (class "Default")
      (node (ref "IC2") (pin "57") (pinfunction "BCBUS5/GPIOH5_57") (pintype "bidirectional"))
    )
    (net (code "123") (name "unconnected-(IC2-BCBUS6{slash}GPIOH6-Pad58)") (class "Default")
      (node (ref "IC2") (pin "58") (pinfunction "BCBUS6/GPIOH6_58") (pintype "bidirectional"))
    )
    (net (code "124") (name "unconnected-(IC2-BCBUS7{slash}GPIOH7-Pad59)") (class "Default")
      (node (ref "IC2") (pin "59") (pinfunction "BCBUS7/GPIOH7_59") (pintype "bidirectional"))
    )
    (net (code "125") (name "unconnected-(IC2-BDBUS4{slash}DTR#{slash}GPIOL0-Pad43)") (class "Default")
      (node (ref "IC2") (pin "43") (pinfunction "BDBUS4/DTR#/GPIOL0_43") (pintype "bidirectional"))
    )
    (net (code "126") (name "unconnected-(IC2-BDBUS5{slash}DSR#{slash}GPIOL1-Pad44)") (class "Default")
      (node (ref "IC2") (pin "44") (pinfunction "BDBUS5/DSR#/GPIOL1_44") (pintype "bidirectional"))
    )
    (net (code "127") (name "unconnected-(IC2-BDBUS6{slash}DCD#{slash}GPIOL2-Pad45)") (class "Default")
      (node (ref "IC2") (pin "45") (pinfunction "BDBUS6/DCD#/GPIOL2_45") (pintype "bidirectional"))
    )
    (net (code "128") (name "unconnected-(IC2-BDBUS7{slash}RI#{slash}GPIOL3-Pad46)") (class "Default")
      (node (ref "IC2") (pin "46") (pinfunction "BDBUS7/RI#/GPIOL3_46") (pintype "bidirectional"))
    )
    (net (code "129") (name "unconnected-(IC2-OSC0-Pad3)") (class "Default")
      (node (ref "IC2") (pin "3") (pinfunction "OSC0_3") (pintype "bidirectional"))
    )
    (net (code "130") (name "unconnected-(IC2-PWREN#-Pad60)") (class "Default")
      (node (ref "IC2") (pin "60") (pinfunction "PWREN#_60") (pintype "bidirectional"))
    )
    (net (code "131") (name "unconnected-(IC2-SUSPEND#-Pad36)") (class "Default")
      (node (ref "IC2") (pin "36") (pinfunction "SUSPEND#_36") (pintype "bidirectional"))
    )
    (net (code "132") (name "unconnected-(Q1-OE-Pad1)") (class "Default")
      (node (ref "Q1") (pin "1") (pinfunction "OE_1") (pintype "input"))
    )
    (net (code "133") (name "unconnected-(Q2-OE-Pad1)") (class "Default")
      (node (ref "Q2") (pin "1") (pinfunction "OE_1") (pintype "input"))
    )
    (net (code "134") (name "unconnected-(U$3A-IO_L01N_0-PadP78)") (class "Default")
      (node (ref "U$3") (pin "P78") (pinfunction "IO_L01N_0_P78") (pintype "bidirectional"))
    )
    (net (code "135") (name "unconnected-(U$3A-IO_L01P_0{slash}VREF_0-PadP77)") (class "Default")
      (node (ref "U$3") (pin "P77") (pinfunction "IO_L01P_0/VREF_0_P77") (pintype "bidirectional"))
    )
    (net (code "136") (name "unconnected-(U$3A-IO_L02N_0{slash}GCLK5-PadP84)") (class "Default")
      (node (ref "U$3") (pin "P84") (pinfunction "IO_L02N_0/GCLK5_P84") (pintype "bidirectional"))
    )
    (net (code "137") (name "unconnected-(U$3A-IO_L03P_0{slash}GCLK6-PadP85)") (class "Default")
      (node (ref "U$3") (pin "P85") (pinfunction "IO_L03P_0/GCLK6_P85") (pintype "bidirectional"))
    )
    (net (code "138") (name "unconnected-(U$3A-IO_L05N_0-PadP94)") (class "Default")
      (node (ref "U$3") (pin "P94") (pinfunction "IO_L05N_0_P94") (pintype "bidirectional"))
    )
    (net (code "139") (name "unconnected-(U$3A-IO_L05P_0-PadP93)") (class "Default")
      (node (ref "U$3") (pin "P93") (pinfunction "IO_L05P_0_P93") (pintype "bidirectional"))
    )
    (net (code "140") (name "unconnected-(U$3A-IO_L06P_0{slash}VREF_0-PadP98)") (class "Default")
      (node (ref "U$3") (pin "P98") (pinfunction "IO_L06P_0/VREF_0_P98") (pintype "bidirectional"))
    )
    (net (code "141") (name "unconnected-(U$3A-IP_0-PadP97)") (class "Default")
      (node (ref "U$3") (pin "P97") (pinfunction "IP_0_P97") (pintype "bidirectional"))
    )
    (net (code "142") (name "unconnected-(U$3A-IP_0{slash}VREF_0-PadP82)") (class "Default")
      (node (ref "U$3") (pin "P82") (pinfunction "IP_0/VREF_0_P82") (pintype "bidirectional"))
    )
    (net (code "143") (name "unconnected-(U$3B-IO_L01N_1-PadP57)") (class "Default")
      (node (ref "U$3") (pin "P57") (pinfunction "IO_L01N_1_P57") (pintype "bidirectional"))
    )
    (net (code "144") (name "unconnected-(U$3B-IO_L01P_1-PadP56)") (class "Default")
      (node (ref "U$3") (pin "P56") (pinfunction "IO_L01P_1_P56") (pintype "bidirectional"))
    )
    (net (code "145") (name "unconnected-(U$3B-IO_L02N_1{slash}RHCLK1-PadP60)") (class "Default")
      (node (ref "U$3") (pin "P60") (pinfunction "IO_L02N_1/RHCLK1_P60") (pintype "bidirectional"))
    )
    (net (code "146") (name "unconnected-(U$3B-IO_L02P_1{slash}RHCLK0-PadP59)") (class "Default")
      (node (ref "U$3") (pin "P59") (pinfunction "IO_L02P_1/RHCLK0_P59") (pintype "bidirectional"))
    )
    (net (code "147") (name "unconnected-(U$3B-IO_L03N_1{slash}TRDY1{slash}RHCLK3-PadP62)") (class "Default")
      (node (ref "U$3") (pin "P62") (pinfunction "IO_L03N_1/TRDY1/RHCLK3_P62") (pintype "bidirectional"))
    )
    (net (code "148") (name "unconnected-(U$3B-IO_L03P_1{slash}RHCLK2-PadP61)") (class "Default")
      (node (ref "U$3") (pin "P61") (pinfunction "IO_L03P_1/RHCLK2_P61") (pintype "bidirectional"))
    )
    (net (code "149") (name "unconnected-(U$3B-IO_L04N_1{slash}RHCLK7-PadP65)") (class "Default")
      (node (ref "U$3") (pin "P65") (pinfunction "IO_L04N_1/RHCLK7_P65") (pintype "bidirectional"))
    )
    (net (code "150") (name "unconnected-(U$3B-IO_L04P_1{slash}IRDY1{slash}RHCLK6-PadP64)") (class "Default")
      (node (ref "U$3") (pin "P64") (pinfunction "IO_L04P_1/IRDY1/RHCLK6_P64") (pintype "bidirectional"))
    )
    (net (code "151") (name "unconnected-(U$3B-IO_L05N_1-PadP71)") (class "Default")
      (node (ref "U$3") (pin "P71") (pinfunction "IO_L05N_1_P71") (pintype "bidirectional"))
    )
    (net (code "152") (name "unconnected-(U$3B-IO_L05P_1-PadP70)") (class "Default")
      (node (ref "U$3") (pin "P70") (pinfunction "IO_L05P_1_P70") (pintype "bidirectional"))
    )
    (net (code "153") (name "unconnected-(U$3B-IO_L06N_1-PadP73)") (class "Default")
      (node (ref "U$3") (pin "P73") (pinfunction "IO_L06N_1_P73") (pintype "bidirectional"))
    )
    (net (code "154") (name "unconnected-(U$3B-IO_L06P_1-PadP72)") (class "Default")
      (node (ref "U$3") (pin "P72") (pinfunction "IO_L06P_1_P72") (pintype "bidirectional"))
    )
    (net (code "155") (name "unconnected-(U$3B-IP_1{slash}VREF_1-PadP68)") (class "Default")
      (node (ref "U$3") (pin "P68") (pinfunction "IP_1/VREF_1_P68") (pintype "bidirectional"))
    )
    (net (code "156") (name "unconnected-(U$3C-IO_2{slash}MOSI{slash}CSI_B-PadP46)") (class "Default")
      (node (ref "U$3") (pin "P46") (pinfunction "IO_2/MOSI/CSI_B_P46") (pintype "bidirectional"))
    )
    (net (code "157") (name "unconnected-(U$3C-IO_L02N_2{slash}CSO_B-PadP27)") (class "Default")
      (node (ref "U$3") (pin "P27") (pinfunction "IO_L02N_2/CSO_B_P27") (pintype "bidirectional"))
    )
    (net (code "158") (name "unconnected-(U$3C-IO_L03N_2{slash}VS2-PadP29)") (class "Default")
      (node (ref "U$3") (pin "P29") (pinfunction "IO_L03N_2/VS2_P29") (pintype "bidirectional"))
    )
    (net (code "159") (name "unconnected-(U$3C-IO_L03P_2{slash}RDWR_B-PadP28)") (class "Default")
      (node (ref "U$3") (pin "P28") (pinfunction "IO_L03P_2/RDWR_B_P28") (pintype "bidirectional"))
    )
    (net (code "160") (name "unconnected-(U$3C-IO_L04N_2{slash}VS0-PadP31)") (class "Default")
      (node (ref "U$3") (pin "P31") (pinfunction "IO_L04N_2/VS0_P31") (pintype "bidirectional"))
    )
    (net (code "161") (name "unconnected-(U$3C-IO_L04P_2{slash}VS1-PadP30)") (class "Default")
      (node (ref "U$3") (pin "P30") (pinfunction "IO_L04P_2/VS1_P30") (pintype "bidirectional"))
    )
    (net (code "162") (name "unconnected-(U$3C-IO_L05N_2-PadP33)") (class "Default")
      (node (ref "U$3") (pin "P33") (pinfunction "IO_L05N_2_P33") (pintype "bidirectional"))
    )
    (net (code "163") (name "unconnected-(U$3C-IO_L05P_2-PadP32)") (class "Default")
      (node (ref "U$3") (pin "P32") (pinfunction "IO_L05P_2_P32") (pintype "bidirectional"))
    )
    (net (code "164") (name "unconnected-(U$3C-IO_L06N_2{slash}D6-PadP35)") (class "Default")
      (node (ref "U$3") (pin "P35") (pinfunction "IO_L06N_2/D6_P35") (pintype "bidirectional"))
    )
    (net (code "165") (name "unconnected-(U$3C-IO_L06P_2{slash}D7-PadP34)") (class "Default")
      (node (ref "U$3") (pin "P34") (pinfunction "IO_L06P_2/D7_P34") (pintype "bidirectional"))
    )
    (net (code "166") (name "unconnected-(U$3C-IO_L07P_2{slash}D5-PadP36)") (class "Default")
      (node (ref "U$3") (pin "P36") (pinfunction "IO_L07P_2/D5_P36") (pintype "bidirectional"))
    )
    (net (code "167") (name "unconnected-(U$3C-IO_L07_2{slash}D4-PadP37)") (class "Default")
      (node (ref "U$3") (pin "P37") (pinfunction "IO_L07_2/D4_P37") (pintype "bidirectional"))
    )
    (net (code "168") (name "unconnected-(U$3C-IO_L08N_2{slash}GCLK15-PadP41)") (class "Default")
      (node (ref "U$3") (pin "P41") (pinfunction "IO_L08N_2/GCLK15_P41") (pintype "bidirectional"))
    )
    (net (code "169") (name "unconnected-(U$3C-IO_L08P_2{slash}GCLK14-PadP40)") (class "Default")
      (node (ref "U$3") (pin "P40") (pinfunction "IO_L08P_2/GCLK14_P40") (pintype "bidirectional"))
    )
    (net (code "170") (name "unconnected-(U$3C-IO_L09N_2{slash}GCLK1-PadP44)") (class "Default")
      (node (ref "U$3") (pin "P44") (pinfunction "IO_L09N_2/GCLK1_P44") (pintype "bidirectional"))
    )
    (net (code "171") (name "unconnected-(U$3C-IO_L09P_2{slash}GCLK0-PadP43)") (class "Default")
      (node (ref "U$3") (pin "P43") (pinfunction "IO_L09P_2/GCLK0_P43") (pintype "bidirectional"))
    )
    (net (code "172") (name "unconnected-(U$3C-IO_L10N_2{slash}D3-PadP49)") (class "Default")
      (node (ref "U$3") (pin "P49") (pinfunction "IO_L10N_2/D3_P49") (pintype "bidirectional"))
    )
    (net (code "173") (name "unconnected-(U$3C-IO_L11N_2{slash}D1-PadP52)") (class "Default")
      (node (ref "U$3") (pin "P52") (pinfunction "IO_L11N_2/D1_P52") (pintype "bidirectional"))
    )
    (net (code "174") (name "unconnected-(U$3C-IO_L11P_2{slash}D2-PadP50)") (class "Default")
      (node (ref "U$3") (pin "P50") (pinfunction "IO_L11P_2/D2_P50") (pintype "bidirectional"))
    )
    (net (code "175") (name "unconnected-(U$3C-IP_2{slash}VREF_2-PadP39)") (class "Default")
      (node (ref "U$3") (pin "P39") (pinfunction "IP_2/VREF_2_P39") (pintype "bidirectional"))
    )
    (net (code "176") (name "unconnected-(U$3D-IO_L03N_3{slash}LHCLK1-PadP10)") (class "Default")
      (node (ref "U$3") (pin "P10") (pinfunction "IO_L03N_3/LHCLK1_P10") (pintype "bidirectional"))
    )
    (net (code "177") (name "unconnected-(U$3D-IO_L03P_3{slash}LHCLK0-PadP9)") (class "Default")
      (node (ref "U$3") (pin "P9") (pinfunction "IO_L03P_3/LHCLK0_P9") (pintype "bidirectional"))
    )
    (net (code "178") (name "unconnected-(U$3D-IO_L04P_3{slash}LHCLK2-PadP12)") (class "Default")
      (node (ref "U$3") (pin "P12") (pinfunction "IO_L04P_3/LHCLK2_P12") (pintype "bidirectional"))
    )
    (net (code "179") (name "unconnected-(U$3D-IO_L06N_3-PadP20)") (class "Default")
      (node (ref "U$3") (pin "P20") (pinfunction "IO_L06N_3_P20") (pintype "bidirectional"))
    )
    (net (code "180") (name "unconnected-(U$3D-IO_L06P_3-PadP19)") (class "Default")
      (node (ref "U$3") (pin "P19") (pinfunction "IO_L06P_3_P19") (pintype "bidirectional"))
    )
    (net (code "181") (name "unconnected-(U$3D-IP_3-PadP21)") (class "Default")
      (node (ref "U$3") (pin "P21") (pinfunction "IP_3_P21") (pintype "bidirectional"))
    )
    (net (code "182") (name "unconnected-(U$3D-IP_3{slash}VREF_3-PadP7)") (class "Default")
      (node (ref "U$3") (pin "P7") (pinfunction "IP_3/VREF_3_P7") (pintype "bidirectional"))
    )
    (net (code "183") (name "unconnected-(U8-(DNC)-Pad16)") (class "Default")
      (node (ref "U8") (pin "16") (pinfunction "(DNC)_16") (pintype "no_connect"))
    )
    (net (code "184") (name "unconnected-(U8-(DNC)_2-Pad12)") (class "Default")
      (node (ref "U8") (pin "12") (pinfunction "(DNC)_2_12") (pintype "no_connect"))
    )
    (net (code "185") (name "unconnected-(U8-(DNC)_3-Pad2)") (class "Default")
      (node (ref "U8") (pin "2") (pinfunction "(DNC)_3_2") (pintype "no_connect"))
    )
    (net (code "186") (name "unconnected-(U8-(DNC)_4-Pad15)") (class "Default")
      (node (ref "U8") (pin "15") (pinfunction "(DNC)_4_15") (pintype "no_connect"))
    )
    (net (code "187") (name "unconnected-(U8-(DNC)_5-Pad9)") (class "Default")
      (node (ref "U8") (pin "9") (pinfunction "(DNC)_5_9") (pintype "no_connect"))
    )
    (net (code "188") (name "unconnected-(U8-(DNC)_6-Pad14)") (class "Default")
      (node (ref "U8") (pin "14") (pinfunction "(DNC)_6_14") (pintype "no_connect"))
    )
    (net (code "189") (name "unconnected-(U8-~{CEO}-Pad13)") (class "Default")
      (node (ref "U8") (pin "13") (pinfunction "~{CEO}_13") (pintype "output"))
    )
  )
)
